# 1.net
KiCad netlist of a schematic drawn in Altium Designer
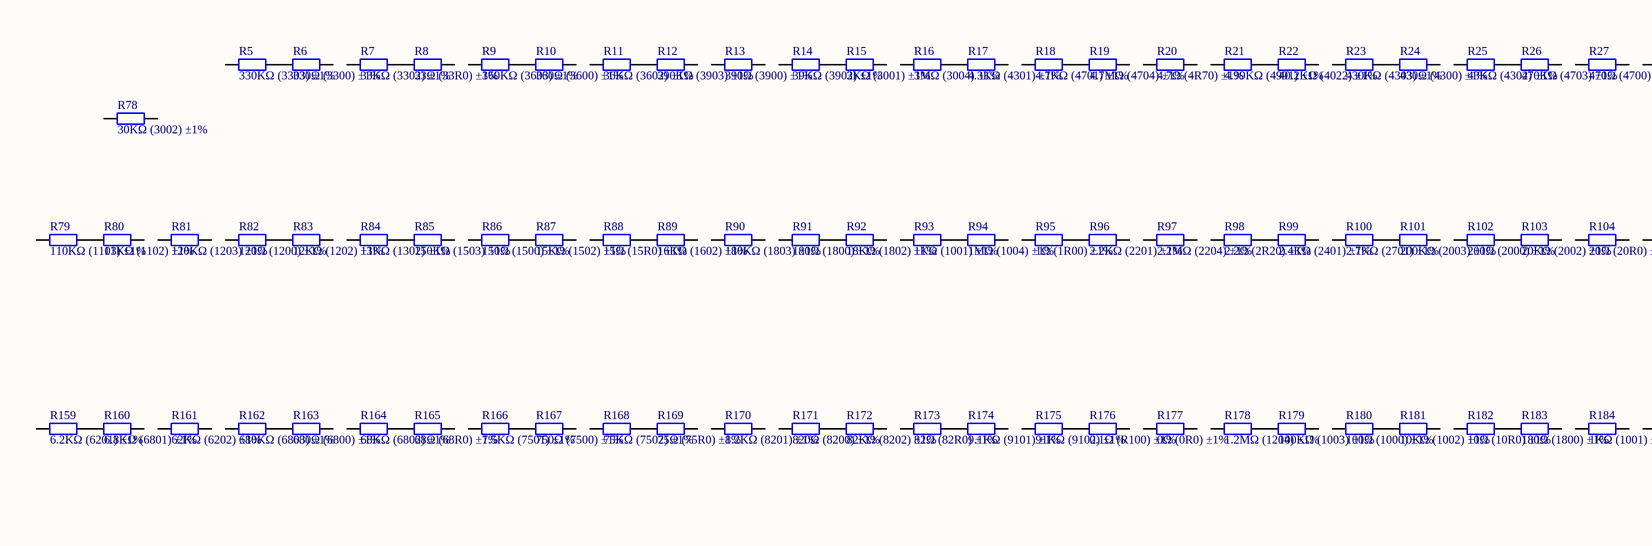
[diagram p0: 1.SchDoc, left]
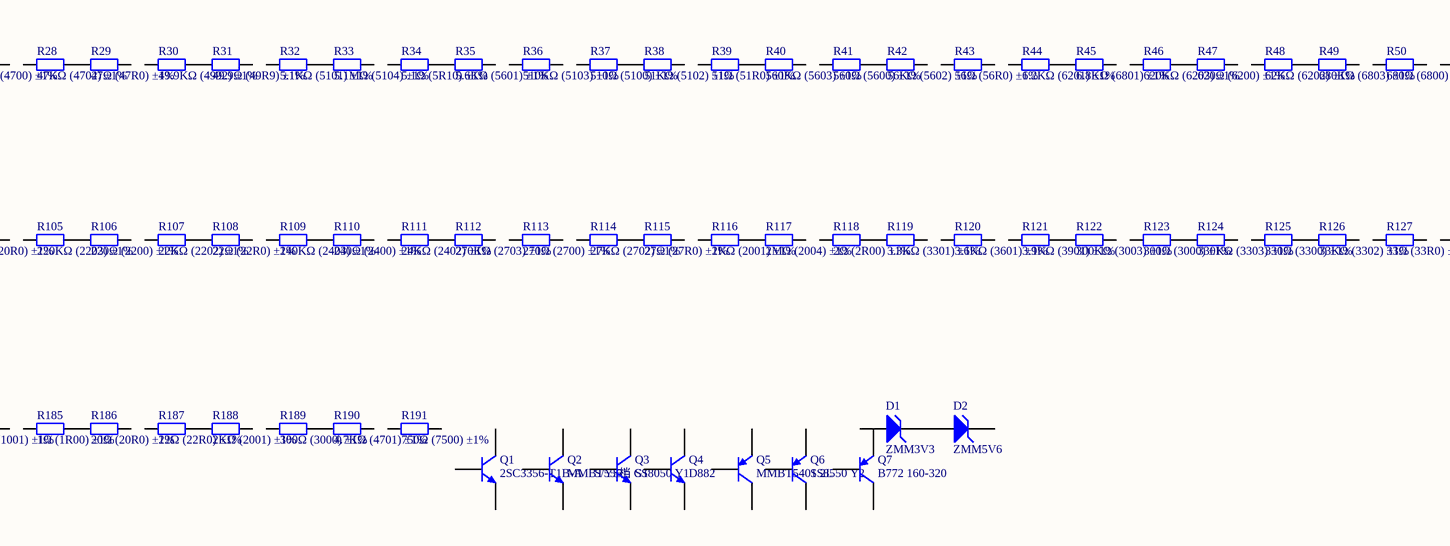
[diagram p1: 1.SchDoc, middle]
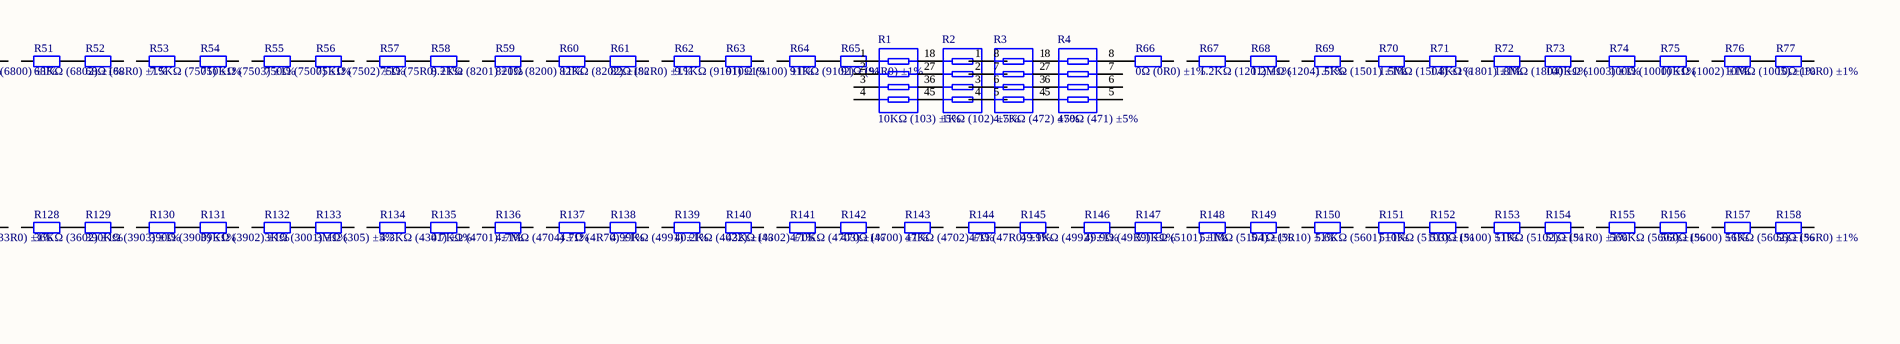
[diagram p2: 1.SchDoc, right]

(export (version "E")
  (design (tool "Eeschema 10.0.6"))
  (components
    (comp (ref "D1")
      (value "ZMM3V3")
      (footprint "LC-LL-34")
      (description "稳压二极管")
      (libsource (lib "Miscellaneous Devices LC") (part "LL-34 ZMM3V3"))
    )
    (comp (ref "D2")
      (value "ZMM5V6")
      (footprint "LC-LL-34")
      (description "稳压二极管")
      (libsource (lib "Miscellaneous Devices LC") (part "LL-34 ZMM5V6"))
    )
    (comp (ref "Q1")
      (value "2SC3356-T1B-A    S/YS档")
      (footprint "LC-SOT-23(SOT-23-3)")
      (description "三极管")
      (libsource (lib "Miscellaneous Devices LC") (part "SOT-23 2SC3356-T1B-A    S/YS档"))
    )
    (comp (ref "Q2")
      (value "MMBT5551  G1")
      (footprint "LC-SOT-23(SOT-23-3)")
      (description "三极管")
      (libsource (lib "Miscellaneous Devices LC") (part "SOT-23 MMBT5551  G1"))
    )
    (comp (ref "Q3")
      (value "SS8050 Y1")
      (footprint "LC-SOT-23(SOT-23-3)")
      (description "三极管")
      (libsource (lib "Miscellaneous Devices LC") (part "SOT-23 SS8050 Y1"))
    )
    (comp (ref "Q4")
      (value "D882")
      (footprint "LC-SOT-89(SOT-89-3)")
      (description "三极管")
      (libsource (lib "Miscellaneous Devices LC") (part "SOT-89 D882"))
    )
    (comp (ref "Q5")
      (value "MMBT5401 2L")
      (footprint "LC-SOT-23(SOT-23-3)")
      (description "三极管")
      (libsource (lib "Miscellaneous Devices LC") (part "SOT-23 MMBT5401 2L"))
    )
    (comp (ref "Q6")
      (value "SS8550 Y2")
      (footprint "LC-SOT-23(SOT-23-3)")
      (description "三极管")
      (libsource (lib "Miscellaneous Devices LC") (part "SOT-23 SS8550 Y2"))
    )
    (comp (ref "Q7")
      (value "B772 160-320")
      (footprint "LC-SOT-89(SOT-89-3)")
      (description "三极管")
      (libsource (lib "Miscellaneous Devices LC") (part "SOT-89 B772 160-320"))
    )
    (comp (ref "R1")
      (value "10KΩ (103) ±5%")
      (footprint "LC-0603_Rx4")
      (description "贴片排阻")
      (libsource (lib "Miscellaneous Devices LC") (part "0603*4  10KΩ (103) 5%"))
    )
    (comp (ref "R2")
      (value "1KΩ (102) ±5%")
      (footprint "LC-0603_Rx4")
      (description "贴片排阻")
      (libsource (lib "Miscellaneous Devices LC") (part "0603*4  1KΩ (102) 5%"))
    )
    (comp (ref "R3")
      (value "4.7KΩ (472) ±5%")
      (footprint "LC-0603_Rx4")
      (description "贴片排阻")
      (libsource (lib "Miscellaneous Devices LC") (part "0603*4  4.7KΩ (472) 5%"))
    )
    (comp (ref "R4")
      (value "470Ω (471) ±5%")
      (footprint "LC-0603_Rx4")
      (description "贴片排阻")
      (libsource (lib "Miscellaneous Devices LC") (part "0603*4 470Ω (471) 5%"))
    )
    (comp (ref "R5")
      (value "330KΩ (3303) ±1%")
      (footprint "LC-0603_R")
      (description "贴片电阻")
      (libsource (lib "Miscellaneous Devices LC") (part "0603 330KΩ (3303) 1%"))
    )
    (comp (ref "R6")
      (value "330Ω (3300) ±1%")
      (footprint "LC-0603_R")
      (description "贴片电阻")
      (libsource (lib "Miscellaneous Devices LC") (part "0603 330Ω (3300) 1%"))
    )
    (comp (ref "R7")
      (value "33KΩ (3302) ±1%")
      (footprint "LC-0603_R")
      (description "贴片电阻")
      (libsource (lib "Miscellaneous Devices LC") (part "0603 33KΩ (3302) 1%"))
    )
    (comp (ref "R8")
      (value "33Ω (33R0) ±1%")
      (footprint "LC-0603_R")
      (description "贴片电阻")
      (libsource (lib "Miscellaneous Devices LC") (part "0603 33Ω (33R0) 1%"))
    )
    (comp (ref "R9")
      (value "360KΩ (3603) ±1%")
      (footprint "LC-0603_R")
      (description "贴片电阻")
      (libsource (lib "Miscellaneous Devices LC") (part "0603 360KΩ (3603) 1%"))
    )
    (comp (ref "R10")
      (value "360Ω (3600) ±1%")
      (footprint "LC-0603_R")
      (description "贴片电阻")
      (libsource (lib "Miscellaneous Devices LC") (part "0603 360Ω (3600) 1%"))
    )
    (comp (ref "R11")
      (value "36KΩ (3602) ±1%")
      (footprint "LC-0603_R")
      (description "贴片电阻")
      (libsource (lib "Miscellaneous Devices LC") (part "0603 36KΩ (3602) 1%"))
    )
    (comp (ref "R12")
      (value "390KΩ (3903) ±1%")
      (footprint "LC-0603_R")
      (description "贴片电阻")
      (libsource (lib "Miscellaneous Devices LC") (part "0603 390KΩ (3903) 1%"))
    )
    (comp (ref "R13")
      (value "390Ω (3900) ±1%")
      (footprint "LC-0603_R")
      (description "贴片电阻")
      (libsource (lib "Miscellaneous Devices LC") (part "0603 390Ω (3900) 1%"))
    )
    (comp (ref "R14")
      (value "39KΩ (3902) ±1%")
      (footprint "LC-0603_R")
      (description "贴片电阻")
      (libsource (lib "Miscellaneous Devices LC") (part "0603 39KΩ (3902) 1%"))
    )
    (comp (ref "R15")
      (value "3KΩ (3001) ±1%")
      (footprint "LC-0603_R")
      (description "贴片电阻")
      (libsource (lib "Miscellaneous Devices LC") (part "0603 3KΩ (3001) 1%"))
    )
    (comp (ref "R16")
      (value "3MΩ (3004) ±1%")
      (footprint "LC-0603_R")
      (description "贴片电阻")
      (libsource (lib "Miscellaneous Devices LC") (part "0603 3MΩ (3004) 1%"))
    )
    (comp (ref "R17")
      (value "4.3KΩ (4301) ±1%")
      (footprint "LC-0603_R")
      (description "贴片电阻")
      (libsource (lib "Miscellaneous Devices LC") (part "0603 4.3KΩ (4301) 1%"))
    )
    (comp (ref "R18")
      (value "4.7KΩ (4701) ±1%")
      (footprint "LC-0603_R")
      (description "贴片电阻")
      (libsource (lib "Miscellaneous Devices LC") (part "0603 4.7KΩ (4701) 1%"))
    )
    (comp (ref "R19")
      (value "4.7MΩ (4704) ±1%")
      (footprint "LC-0603_R")
      (description "贴片电阻")
      (libsource (lib "Miscellaneous Devices LC") (part "0603 4.7MΩ (4704) 1%"))
    )
    (comp (ref "R20")
      (value "4.7Ω (4R70) ±1%")
      (footprint "LC-0603_R")
      (description "贴片电阻")
      (libsource (lib "Miscellaneous Devices LC") (part "0603 4.7Ω (4R70) 1%"))
    )
    (comp (ref "R21")
      (value "4.99KΩ (4991) ±1%")
      (footprint "LC-0603_R")
      (description "贴片电阻")
      (libsource (lib "Miscellaneous Devices LC") (part "0603 4.99KΩ (4991) 1%"))
    )
    (comp (ref "R22")
      (value "40.2KΩ (4022) ±1%")
      (footprint "LC-0603_R")
      (description "贴片电阻")
      (libsource (lib "Miscellaneous Devices LC") (part "0603 40.2KΩ (4022) 1%"))
    )
    (comp (ref "R23")
      (value "430KΩ (4303) ±1%")
      (footprint "LC-0603_R")
      (description "贴片电阻")
      (libsource (lib "Miscellaneous Devices LC") (part "0603 430KΩ (4303) 1%"))
    )
    (comp (ref "R24")
      (value "430Ω (4300) ±1%")
      (footprint "LC-0603_R")
      (description "贴片电阻")
      (libsource (lib "Miscellaneous Devices LC") (part "0603 430Ω (4300) 1%"))
    )
    (comp (ref "R25")
      (value "43KΩ (4302) ±1%")
      (footprint "LC-0603_R")
      (description "贴片电阻")
      (libsource (lib "Miscellaneous Devices LC") (part "0603 43KΩ (4302) 1%"))
    )
    (comp (ref "R26")
      (value "470KΩ (4703) ±1%")
      (footprint "LC-0603_R")
      (description "贴片电阻")
      (libsource (lib "Miscellaneous Devices LC") (part "0603 470KΩ (4703) 1%"))
    )
    (comp (ref "R27")
      (value "470Ω (4700) ±1%")
      (footprint "LC-0603_R")
      (description "贴片电阻")
      (libsource (lib "Miscellaneous Devices LC") (part "0603 470Ω (4700) 1%"))
    )
    (comp (ref "R28")
      (value "47KΩ (4702) ±1%")
      (footprint "LC-0603_R")
      (description "贴片电阻")
      (libsource (lib "Miscellaneous Devices LC") (part "0603 47KΩ (4702) 1%"))
    )
    (comp (ref "R29")
      (value "47Ω (47R0) ±1%")
      (footprint "LC-0603_R")
      (description "贴片电阻")
      (libsource (lib "Miscellaneous Devices LC") (part "0603 47Ω (47R0) 1%"))
    )
    (comp (ref "R30")
      (value "49.9KΩ (4992) ±1%")
      (footprint "LC-0603_R")
      (description "贴片电阻")
      (libsource (lib "Miscellaneous Devices LC") (part "0603 49.9KΩ (4992) 1%"))
    )
    (comp (ref "R31")
      (value "49.9Ω (49R9) ±1%")
      (footprint "LC-0603_R")
      (description "贴片电阻")
      (libsource (lib "Miscellaneous Devices LC") (part "0603 49.9Ω (49R9) 1%"))
    )
    (comp (ref "R32")
      (value "5.1KΩ (5101) ±1%")
      (footprint "LC-0603_R")
      (description "贴片电阻")
      (libsource (lib "Miscellaneous Devices LC") (part "0603 5.1KΩ (5101) 1%"))
    )
    (comp (ref "R33")
      (value "5.1MΩ (5104) ±1%")
      (footprint "LC-0603_R")
      (description "贴片电阻")
      (libsource (lib "Miscellaneous Devices LC") (part "0603 5.1MΩ (5104) 1%"))
    )
    (comp (ref "R34")
      (value "5.1Ω (5R10) ±1%")
      (footprint "LC-0603_R")
      (description "贴片电阻")
      (libsource (lib "Miscellaneous Devices LC") (part "0603 5.1Ω (5R10) 1%"))
    )
    (comp (ref "R35")
      (value "5.6KΩ (5601) ±1%")
      (footprint "LC-0603_R")
      (description "贴片电阻")
      (libsource (lib "Miscellaneous Devices LC") (part "0603 5.6KΩ (5601) 1%"))
    )
    (comp (ref "R36")
      (value "510KΩ (5103) ±1%")
      (footprint "LC-0603_R")
      (description "贴片电阻")
      (libsource (lib "Miscellaneous Devices LC") (part "0603 510KΩ (5103) 1%"))
    )
    (comp (ref "R37")
      (value "510Ω (5100) ±1%")
      (footprint "LC-0603_R")
      (description "贴片电阻")
      (libsource (lib "Miscellaneous Devices LC") (part "0603 510Ω (5100) 1%"))
    )
    (comp (ref "R38")
      (value "51KΩ (5102) ±1%")
      (footprint "LC-0603_R")
      (description "贴片电阻")
      (libsource (lib "Miscellaneous Devices LC") (part "0603 51KΩ (5102) 1%"))
    )
    (comp (ref "R39")
      (value "51Ω (51R0) ±1%")
      (footprint "LC-0603_R")
      (description "贴片电阻")
      (libsource (lib "Miscellaneous Devices LC") (part "0603 51Ω (51R0) 1%"))
    )
    (comp (ref "R40")
      (value "560KΩ (5603) ±1%")
      (footprint "LC-0603_R")
      (description "贴片电阻")
      (libsource (lib "Miscellaneous Devices LC") (part "0603 560KΩ (5603) 1%"))
    )
    (comp (ref "R41")
      (value "560Ω (5600) ±1%")
      (footprint "LC-0603_R")
      (description "贴片电阻")
      (libsource (lib "Miscellaneous Devices LC") (part "0603 560Ω (5600) 1%"))
    )
    (comp (ref "R42")
      (value "56KΩ (5602) ±1%")
      (footprint "LC-0603_R")
      (description "贴片电阻")
      (libsource (lib "Miscellaneous Devices LC") (part "0603 56KΩ (5602) 1%"))
    )
    (comp (ref "R43")
      (value "56Ω (56R0) ±1%")
      (footprint "LC-0603_R")
      (description "贴片电阻")
      (libsource (lib "Miscellaneous Devices LC") (part "0603 56Ω (56R0) 1%"))
    )
    (comp (ref "R44")
      (value "6.2KΩ (6201) ±1%")
      (footprint "LC-0603_R")
      (description "贴片电阻")
      (libsource (lib "Miscellaneous Devices LC") (part "0603 6.2KΩ (6201) 1%"))
    )
    (comp (ref "R45")
      (value "6.8KΩ (6801) ±1%")
      (footprint "LC-0603_R")
      (description "贴片电阻")
      (libsource (lib "Miscellaneous Devices LC") (part "0603 6.8KΩ (6801) 1%"))
    )
    (comp (ref "R46")
      (value "620KΩ (6203) ±1%")
      (footprint "LC-0603_R")
      (description "贴片电阻")
      (libsource (lib "Miscellaneous Devices LC") (part "0603 620KΩ (6203) 1%"))
    )
    (comp (ref "R47")
      (value "620Ω (6200) ±1%")
      (footprint "LC-0603_R")
      (description "贴片电阻")
      (libsource (lib "Miscellaneous Devices LC") (part "0603 620Ω (6200) 1%"))
    )
    (comp (ref "R48")
      (value "62KΩ (6202) ±1%")
      (footprint "LC-0603_R")
      (description "贴片电阻")
      (libsource (lib "Miscellaneous Devices LC") (part "0603 62KΩ (6202) 1%"))
    )
    (comp (ref "R49")
      (value "680KΩ (6803) ±1%")
      (footprint "LC-0603_R")
      (description "贴片电阻")
      (libsource (lib "Miscellaneous Devices LC") (part "0603 680KΩ (6803) 1%"))
    )
    (comp (ref "R50")
      (value "680Ω (6800) ±1%")
      (footprint "LC-0603_R")
      (description "贴片电阻")
      (libsource (lib "Miscellaneous Devices LC") (part "0603 680Ω (6800) 1%"))
    )
    (comp (ref "R51")
      (value "68KΩ (6802) ±1%")
      (footprint "LC-0603_R")
      (description "贴片电阻")
      (libsource (lib "Miscellaneous Devices LC") (part "0603 68KΩ (6802) 1%"))
    )
    (comp (ref "R52")
      (value "68Ω (68R0) ±1%")
      (footprint "LC-0603_R")
      (description "贴片电阻")
      (libsource (lib "Miscellaneous Devices LC") (part "0603 68Ω (68R0) 1%"))
    )
    (comp (ref "R53")
      (value "7.5KΩ (7501) ±1%")
      (footprint "LC-0603_R")
      (description "贴片电阻")
      (libsource (lib "Miscellaneous Devices LC") (part "0603 7.5KΩ (7501) 1%"))
    )
    (comp (ref "R54")
      (value "750KΩ (7503) ±1%")
      (footprint "LC-0603_R")
      (description "贴片电阻")
      (libsource (lib "Miscellaneous Devices LC") (part "0603 750KΩ (7503) 1%"))
    )
    (comp (ref "R55")
      (value "750Ω (7500) ±1%")
      (footprint "LC-0603_R")
      (description "贴片电阻")
      (libsource (lib "Miscellaneous Devices LC") (part "0603 750Ω (7500) 1%"))
    )
    (comp (ref "R56")
      (value "75KΩ (7502) ±1%")
      (footprint "LC-0603_R")
      (description "贴片电阻")
      (libsource (lib "Miscellaneous Devices LC") (part "0603 75KΩ (7502) 1%"))
    )
    (comp (ref "R57")
      (value "75Ω (75R0) ±1%")
      (footprint "LC-0603_R")
      (description "贴片电阻")
      (libsource (lib "Miscellaneous Devices LC") (part "0603 75Ω (75R0) 1%"))
    )
    (comp (ref "R58")
      (value "8.2KΩ (8201) ±1%")
      (footprint "LC-0603_R")
      (description "贴片电阻")
      (libsource (lib "Miscellaneous Devices LC") (part "0603 8.2KΩ (8201) 1%"))
    )
    (comp (ref "R59")
      (value "820Ω (8200) ±1%")
      (footprint "LC-0603_R")
      (description "贴片电阻")
      (libsource (lib "Miscellaneous Devices LC") (part "0603 820Ω (8200) 1%"))
    )
    (comp (ref "R60")
      (value "82KΩ (8202) ±1%")
      (footprint "LC-0603_R")
      (description "贴片电阻")
      (libsource (lib "Miscellaneous Devices LC") (part "0603 82KΩ (8202) 1%"))
    )
    (comp (ref "R61")
      (value "82Ω (82R0) ±1%")
      (footprint "LC-0603_R")
      (description "贴片电阻")
      (libsource (lib "Miscellaneous Devices LC") (part "0603 82Ω (82R0) 1%"))
    )
    (comp (ref "R62")
      (value "9.1KΩ (9101) ±1%")
      (footprint "LC-0603_R")
      (description "贴片电阻")
      (libsource (lib "Miscellaneous Devices LC") (part "0603 9.1KΩ (9101) 1%"))
    )
    (comp (ref "R63")
      (value "910Ω (9100) ±1%")
      (footprint "LC-0603_R")
      (description "贴片电阻")
      (libsource (lib "Miscellaneous Devices LC") (part "0603 910Ω (9100) 1%"))
    )
    (comp (ref "R64")
      (value "91KΩ (9102) ±1%")
      (footprint "LC-0603_R")
      (description "贴片电阻")
      (libsource (lib "Miscellaneous Devices LC") (part "0603 91KΩ (9102) 1%"))
    )
    (comp (ref "R65")
      (value "91Ω (91R0) ±1%")
      (footprint "LC-0603_R")
      (description "贴片电阻")
      (libsource (lib "Miscellaneous Devices LC") (part "0603 91Ω (91R0) 1%"))
    )
    (comp (ref "R66")
      (value "0Ω (0R0) ±1%")
      (footprint "LC-0805_R")
      (description "贴片电阻")
      (libsource (lib "Miscellaneous Devices LC") (part "0805 0Ω (0R0) 1%"))
    )
    (comp (ref "R67")
      (value "1.2KΩ (1201) ±1%")
      (footprint "LC-0805_R")
      (description "贴片电阻")
      (libsource (lib "Miscellaneous Devices LC") (part "0805 1.2KΩ (1201) 1%"))
    )
    (comp (ref "R68")
      (value "1.2MΩ (1204) ±1%")
      (footprint "LC-0805_R")
      (description "贴片电阻")
      (libsource (lib "Miscellaneous Devices LC") (part "0805 1.2MΩ (1204) 1%"))
    )
    (comp (ref "R69")
      (value "1.5KΩ (1501) ±1%")
      (footprint "LC-0805_R")
      (description "贴片电阻")
      (libsource (lib "Miscellaneous Devices LC") (part "0805 1.5KΩ (1501) 1%"))
    )
    (comp (ref "R70")
      (value "1.5MΩ (1504) ±1%")
      (footprint "LC-0805_R")
      (description "贴片电阻")
      (libsource (lib "Miscellaneous Devices LC") (part "0805 1.5MΩ (1504) 1%"))
    )
    (comp (ref "R71")
      (value "1.8KΩ (1801) ±1%")
      (footprint "LC-0805_R")
      (description "贴片电阻")
      (libsource (lib "Miscellaneous Devices LC") (part "0805 1.8KΩ (1801) 1%"))
    )
    (comp (ref "R72")
      (value "1.8MΩ (1804) ±1%")
      (footprint "LC-0805_R")
      (description "贴片电阻")
      (libsource (lib "Miscellaneous Devices LC") (part "0805 1.8MΩ (1804) 1%"))
    )
    (comp (ref "R73")
      (value "100KΩ (1003) ±1%")
      (footprint "LC-0805_R")
      (description "贴片电阻")
      (libsource (lib "Miscellaneous Devices LC") (part "0805 100KΩ (1003) 1%"))
    )
    (comp (ref "R74")
      (value "100Ω (1000) ±1%")
      (footprint "LC-0805_R")
      (description "贴片电阻")
      (libsource (lib "Miscellaneous Devices LC") (part "0805 100Ω (1000) 1%"))
    )
    (comp (ref "R75")
      (value "10KΩ (1002) ±1%")
      (footprint "LC-0805_R")
      (description "贴片电阻")
      (libsource (lib "Miscellaneous Devices LC") (part "0805 10KΩ (1002) 1%"))
    )
    (comp (ref "R76")
      (value "10MΩ (1005) ±1%")
      (footprint "LC-0805_R")
      (description "贴片电阻")
      (libsource (lib "Miscellaneous Devices LC") (part "0805 10MΩ (1005) 1%"))
    )
    (comp (ref "R77")
      (value "10Ω (10R0) ±1%")
      (footprint "LC-0805_R")
      (description "贴片电阻")
      (libsource (lib "Miscellaneous Devices LC") (part "0805 10Ω (10R0) 1%"))
    )
    (comp (ref "R78")
      (value "30KΩ (3002) ±1%")
      (footprint "LC-0603_R")
      (description "贴片电阻")
      (libsource (lib "Miscellaneous Devices LC") (part "0603 30KΩ (3002) 1%"))
    )
    (comp (ref "R79")
      (value "110KΩ (1103) ±1%")
      (footprint "LC-0805_R")
      (description "贴片电阻")
      (libsource (lib "Miscellaneous Devices LC") (part "0805 110KΩ (1103) 1%"))
    )
    (comp (ref "R80")
      (value "11KΩ (1102) ±1%")
      (footprint "LC-0805_R")
      (description "贴片电阻")
      (libsource (lib "Miscellaneous Devices LC") (part "0805 11KΩ (1102) 1%"))
    )
    (comp (ref "R81")
      (value "120KΩ (1203) ±1%")
      (footprint "LC-0805_R")
      (description "贴片电阻")
      (libsource (lib "Miscellaneous Devices LC") (part "0805 120KΩ (1203) 1%"))
    )
    (comp (ref "R82")
      (value "120Ω (1200) ±1%")
      (footprint "LC-0805_R")
      (description "贴片电阻")
      (libsource (lib "Miscellaneous Devices LC") (part "0805 120Ω (1200) 1%"))
    )
    (comp (ref "R83")
      (value "12KΩ (1202) ±1%")
      (footprint "LC-0805_R")
      (description "贴片电阻")
      (libsource (lib "Miscellaneous Devices LC") (part "0805 12KΩ (1202) 1%"))
    )
    (comp (ref "R84")
      (value "13KΩ (1302) ±1%")
      (footprint "LC-0805_R")
      (description "贴片电阻")
      (libsource (lib "Miscellaneous Devices LC") (part "0805 13KΩ (1302) 1%"))
    )
    (comp (ref "R85")
      (value "150KΩ (1503) ±1%")
      (footprint "LC-0805_R")
      (description "贴片电阻")
      (libsource (lib "Miscellaneous Devices LC") (part "0805 150KΩ (1503) 1%"))
    )
    (comp (ref "R86")
      (value "150Ω (1500) ±1%")
      (footprint "LC-0805_R")
      (description "贴片电阻")
      (libsource (lib "Miscellaneous Devices LC") (part "0805 150Ω (1500) 1%"))
    )
    (comp (ref "R87")
      (value "15KΩ (1502) ±1%")
      (footprint "LC-0805_R")
      (description "贴片电阻")
      (libsource (lib "Miscellaneous Devices LC") (part "0805 15KΩ (1502) 1%"))
    )
    (comp (ref "R88")
      (value "15Ω (15R0) ±1%")
      (footprint "LC-0805_R")
      (description "贴片电阻")
      (libsource (lib "Miscellaneous Devices LC") (part "0805 15Ω (15R0) 1%"))
    )
    (comp (ref "R89")
      (value "16KΩ (1602) ±1%")
      (footprint "LC-0805_R")
      (description "贴片电阻")
      (libsource (lib "Miscellaneous Devices LC") (part "0805 16KΩ (1602) 1%"))
    )
    (comp (ref "R90")
      (value "180KΩ (1803) ±1%")
      (footprint "LC-0805_R")
      (description "贴片电阻")
      (libsource (lib "Miscellaneous Devices LC") (part "0805 180KΩ (1803) 1%"))
    )
    (comp (ref "R91")
      (value "180Ω (1800) ±1%")
      (footprint "LC-0805_R")
      (description "贴片电阻")
      (libsource (lib "Miscellaneous Devices LC") (part "0805 180Ω (1800) 1%"))
    )
    (comp (ref "R92")
      (value "18KΩ (1802) ±1%")
      (footprint "LC-0805_R")
      (description "贴片电阻")
      (libsource (lib "Miscellaneous Devices LC") (part "0805 18KΩ (1802) 1%"))
    )
    (comp (ref "R93")
      (value "1KΩ (1001) ±1%")
      (footprint "LC-0805_R")
      (description "贴片电阻")
      (libsource (lib "Miscellaneous Devices LC") (part "0805 1KΩ (1001) 1%"))
    )
    (comp (ref "R94")
      (value "1MΩ (1004) ±1%")
      (footprint "LC-0805_R")
      (description "贴片电阻")
      (libsource (lib "Miscellaneous Devices LC") (part "0805 1MΩ (1004) 1%"))
    )
    (comp (ref "R95")
      (value "1Ω (1R00) ±1%")
      (footprint "LC-0805_R")
      (description "贴片电阻")
      (libsource (lib "Miscellaneous Devices LC") (part "0805 1Ω (1R00) 1%"))
    )
    (comp (ref "R96")
      (value "2.2KΩ (2201) ±1%")
      (footprint "LC-0805_R")
      (description "贴片电阻")
      (libsource (lib "Miscellaneous Devices LC") (part "0805 2.2KΩ (2201) 1%"))
    )
    (comp (ref "R97")
      (value "2.2MΩ (2204) ±1%")
      (footprint "LC-0805_R")
      (description "贴片电阻")
      (libsource (lib "Miscellaneous Devices LC") (part "0805 2.2MΩ (2204) 1%"))
    )
    (comp (ref "R98")
      (value "2.2Ω (2R20) ±1%")
      (footprint "LC-0805_R")
      (description "贴片电阻")
      (libsource (lib "Miscellaneous Devices LC") (part "0805 2.2Ω (2R20) 1%"))
    )
    (comp (ref "R99")
      (value "2.4KΩ (2401) ±1%")
      (footprint "LC-0805_R")
      (description "贴片电阻")
      (libsource (lib "Miscellaneous Devices LC") (part "0805 2.4KΩ (2401) 1%"))
    )
    (comp (ref "R100")
      (value "2.7KΩ (2701) ±1%")
      (footprint "LC-0805_R")
      (description "贴片电阻")
      (libsource (lib "Miscellaneous Devices LC") (part "0805 2.7KΩ (2701) 1%"))
    )
    (comp (ref "R101")
      (value "200KΩ (2003) ±1%")
      (footprint "LC-0805_R")
      (description "贴片电阻")
      (libsource (lib "Miscellaneous Devices LC") (part "0805 200KΩ (2003) 1%"))
    )
    (comp (ref "R102")
      (value "200Ω (2000) ±1%")
      (footprint "LC-0805_R")
      (description "贴片电阻")
      (libsource (lib "Miscellaneous Devices LC") (part "0805 200Ω (2000) 1%"))
    )
    (comp (ref "R103")
      (value "20KΩ (2002) ±1%")
      (footprint "LC-0805_R")
      (description "贴片电阻")
      (libsource (lib "Miscellaneous Devices LC") (part "0805 20KΩ (2002) 1%"))
    )
    (comp (ref "R104")
      (value "20Ω (20R0) ±1%")
      (footprint "LC-0805_R")
      (description "贴片电阻")
      (libsource (lib "Miscellaneous Devices LC") (part "0805 20Ω (20R0) 1%"))
    )
    (comp (ref "R105")
      (value "220KΩ (2203) ±1%")
      (footprint "LC-0805_R")
      (description "贴片电阻")
      (libsource (lib "Miscellaneous Devices LC") (part "0805 220KΩ (2203) 1%"))
    )
    (comp (ref "R106")
      (value "220Ω (2200) ±1%")
      (footprint "LC-0805_R")
      (description "贴片电阻")
      (libsource (lib "Miscellaneous Devices LC") (part "0805 220Ω (2200) 1%"))
    )
    (comp (ref "R107")
      (value "22KΩ (2202) ±1%")
      (footprint "LC-0805_R")
      (description "贴片电阻")
      (libsource (lib "Miscellaneous Devices LC") (part "0805 22KΩ (2202) 1%"))
    )
    (comp (ref "R108")
      (value "22Ω (22R0) ±1%")
      (footprint "LC-0805_R")
      (description "贴片电阻")
      (libsource (lib "Miscellaneous Devices LC") (part "0805 22Ω (22R0) 1%"))
    )
    (comp (ref "R109")
      (value "240KΩ (2403) ±1%")
      (footprint "LC-0805_R")
      (description "贴片电阻")
      (libsource (lib "Miscellaneous Devices LC") (part "0805 240KΩ (2403) 1%"))
    )
    (comp (ref "R110")
      (value "240Ω (2400) ±1%")
      (footprint "LC-0805_R")
      (description "贴片电阻")
      (libsource (lib "Miscellaneous Devices LC") (part "0805 240Ω (2400) 1%"))
    )
    (comp (ref "R111")
      (value "24KΩ (2402) ±1%")
      (footprint "LC-0805_R")
      (description "贴片电阻")
      (libsource (lib "Miscellaneous Devices LC") (part "0805 24KΩ (2402) 1%"))
    )
    (comp (ref "R112")
      (value "270KΩ (2703) ±1%")
      (footprint "LC-0805_R")
      (description "贴片电阻")
      (libsource (lib "Miscellaneous Devices LC") (part "0805 270KΩ (2703) 1%"))
    )
    (comp (ref "R113")
      (value "270Ω (2700) ±1%")
      (footprint "LC-0805_R")
      (description "贴片电阻")
      (libsource (lib "Miscellaneous Devices LC") (part "0805 270Ω (2700) 1%"))
    )
    (comp (ref "R114")
      (value "27KΩ (2702) ±1%")
      (footprint "LC-0805_R")
      (description "贴片电阻")
      (libsource (lib "Miscellaneous Devices LC") (part "0805 27KΩ (2702) 1%"))
    )
    (comp (ref "R115")
      (value "27Ω (27R0) ±1%")
      (footprint "LC-0805_R")
      (description "贴片电阻")
      (libsource (lib "Miscellaneous Devices LC") (part "0805 27Ω (27R0) 1%"))
    )
    (comp (ref "R116")
      (value "2KΩ (2001) ±1%")
      (footprint "LC-0805_R")
      (description "贴片电阻")
      (libsource (lib "Miscellaneous Devices LC") (part "0805 2KΩ (2001) 1%"))
    )
    (comp (ref "R117")
      (value "2MΩ (2004) ±1%")
      (footprint "LC-0805_R")
      (description "贴片电阻")
      (libsource (lib "Miscellaneous Devices LC") (part "0805 2MΩ (2004) 1%"))
    )
    (comp (ref "R118")
      (value "2Ω (2R00) ±1%")
      (footprint "LC-0805_R")
      (description "贴片电阻")
      (libsource (lib "Miscellaneous Devices LC") (part "0805 2Ω (2R00) 1%"))
    )
    (comp (ref "R119")
      (value "3.3KΩ (3301) ±1%")
      (footprint "LC-0805_R")
      (description "贴片电阻")
      (libsource (lib "Miscellaneous Devices LC") (part "0805 3.3KΩ (3301) 1%"))
    )
    (comp (ref "R120")
      (value "3.6KΩ (3601) ±1%")
      (footprint "LC-0805_R")
      (description "贴片电阻")
      (libsource (lib "Miscellaneous Devices LC") (part "0805 3.6KΩ (3601) 1%"))
    )
    (comp (ref "R121")
      (value "3.9KΩ (3901) ±1%")
      (footprint "LC-0805_R")
      (description "贴片电阻")
      (libsource (lib "Miscellaneous Devices LC") (part "0805 3.9KΩ (3901) 1%"))
    )
    (comp (ref "R122")
      (value "300KΩ (3003) ±1%")
      (footprint "LC-0805_R")
      (description "贴片电阻")
      (libsource (lib "Miscellaneous Devices LC") (part "0805 300KΩ (3003) 1%"))
    )
    (comp (ref "R123")
      (value "300Ω (3000) ±1%")
      (footprint "LC-0805_R")
      (description "贴片电阻")
      (libsource (lib "Miscellaneous Devices LC") (part "0805 300Ω (3000) 1%"))
    )
    (comp (ref "R124")
      (value "330KΩ (3303) ±1%")
      (footprint "LC-0805_R")
      (description "贴片电阻")
      (libsource (lib "Miscellaneous Devices LC") (part "0805 330KΩ (3303) 1%"))
    )
    (comp (ref "R125")
      (value "330Ω (3300) ±1%")
      (footprint "LC-0805_R")
      (description "贴片电阻")
      (libsource (lib "Miscellaneous Devices LC") (part "0805 330Ω (3300) 1%"))
    )
    (comp (ref "R126")
      (value "33KΩ (3302) ±1%")
      (footprint "LC-0805_R")
      (description "贴片电阻")
      (libsource (lib "Miscellaneous Devices LC") (part "0805 33KΩ (3302) 1%"))
    )
    (comp (ref "R127")
      (value "33Ω (33R0) ±1%")
      (footprint "LC-0805_R")
      (description "贴片电阻")
      (libsource (lib "Miscellaneous Devices LC") (part "0805 33Ω (33R0) 1%"))
    )
    (comp (ref "R128")
      (value "36KΩ (3602) ±1%")
      (footprint "LC-0805_R")
      (description "贴片电阻")
      (libsource (lib "Miscellaneous Devices LC") (part "0805 36KΩ (3602) 1%"))
    )
    (comp (ref "R129")
      (value "390KΩ (3903) ±1%")
      (footprint "LC-0805_R")
      (description "贴片电阻")
      (libsource (lib "Miscellaneous Devices LC") (part "0805 390KΩ (3903) 1%"))
    )
    (comp (ref "R130")
      (value "390Ω (3900) ±1%")
      (footprint "LC-0805_R")
      (description "贴片电阻")
      (libsource (lib "Miscellaneous Devices LC") (part "0805 390Ω (3900) 1%"))
    )
    (comp (ref "R131")
      (value "39KΩ (3902) ±1%")
      (footprint "LC-0805_R")
      (description "贴片电阻")
      (libsource (lib "Miscellaneous Devices LC") (part "0805 39KΩ (3902) 1%"))
    )
    (comp (ref "R132")
      (value "3KΩ (3001) ±1%")
      (footprint "LC-0805_R")
      (description "贴片电阻")
      (libsource (lib "Miscellaneous Devices LC") (part "0805 3KΩ (3001) 1%"))
    )
    (comp (ref "R133")
      (value "3MΩ (305) ±5%")
      (footprint "LC-0805_R")
      (description "贴片电阻")
      (libsource (lib "Miscellaneous Devices LC") (part "0805 3MΩ (305) 5%"))
    )
    (comp (ref "R134")
      (value "4.3KΩ (4301) ±1%")
      (footprint "LC-0805_R")
      (description "贴片电阻")
      (libsource (lib "Miscellaneous Devices LC") (part "0805 4.3KΩ (4301) 1%"))
    )
    (comp (ref "R135")
      (value "4.7KΩ (4701) ±1%")
      (footprint "LC-0805_R")
      (description "贴片电阻")
      (libsource (lib "Miscellaneous Devices LC") (part "0805 4.7KΩ (4701) 1%"))
    )
    (comp (ref "R136")
      (value "4.7MΩ (4704) ±1%")
      (footprint "LC-0805_R")
      (description "贴片电阻")
      (libsource (lib "Miscellaneous Devices LC") (part "0805 4.7MΩ (4704) 1%"))
    )
    (comp (ref "R137")
      (value "4.7Ω (4R70) ±1%")
      (footprint "LC-0805_R")
      (description "贴片电阻")
      (libsource (lib "Miscellaneous Devices LC") (part "0805 4.7Ω (4R70) 1%"))
    )
    (comp (ref "R138")
      (value "4.99KΩ (4991) ±1%")
      (footprint "LC-0805_R")
      (description "贴片电阻")
      (libsource (lib "Miscellaneous Devices LC") (part "0805 4.99KΩ (4991) 1%"))
    )
    (comp (ref "R139")
      (value "40.2KΩ (4022) ±1%")
      (footprint "LC-0805_R")
      (description "贴片电阻")
      (libsource (lib "Miscellaneous Devices LC") (part "0805 40.2KΩ (4022) 1%"))
    )
    (comp (ref "R140")
      (value "43KΩ (4302) ±1%")
      (footprint "LC-0805_R")
      (description "贴片电阻")
      (libsource (lib "Miscellaneous Devices LC") (part "0805 43KΩ (4302) 1%"))
    )
    (comp (ref "R141")
      (value "470KΩ (4703) ±1%")
      (footprint "LC-0805_R")
      (description "贴片电阻")
      (libsource (lib "Miscellaneous Devices LC") (part "0805 470KΩ (4703) 1%"))
    )
    (comp (ref "R142")
      (value "470Ω (4700) ±1%")
      (footprint "LC-0805_R")
      (description "贴片电阻")
      (libsource (lib "Miscellaneous Devices LC") (part "0805 470Ω (4700) 1%"))
    )
    (comp (ref "R143")
      (value "47KΩ (4702) ±1%")
      (footprint "LC-0805_R")
      (description "贴片电阻")
      (libsource (lib "Miscellaneous Devices LC") (part "0805 47KΩ (4702) 1%"))
    )
    (comp (ref "R144")
      (value "47Ω (47R0) ±1%")
      (footprint "LC-0805_R")
      (description "贴片电阻")
      (libsource (lib "Miscellaneous Devices LC") (part "0805 47Ω (47R0) 1%"))
    )
    (comp (ref "R145")
      (value "49.9KΩ (4992) ±1%")
      (footprint "LC-0805_R")
      (description "贴片电阻")
      (libsource (lib "Miscellaneous Devices LC") (part "0805 49.9KΩ (4992) 1%"))
    )
    (comp (ref "R146")
      (value "49.9Ω (49R9) ±1%")
      (footprint "LC-0805_R")
      (description "贴片电阻")
      (libsource (lib "Miscellaneous Devices LC") (part "0805 49.9Ω (49R9) 1%"))
    )
    (comp (ref "R147")
      (value "5.1KΩ (5101) ±1%")
      (footprint "LC-0805_R")
      (description "贴片电阻")
      (libsource (lib "Miscellaneous Devices LC") (part "0805 5.1KΩ (5101) 1%"))
    )
    (comp (ref "R148")
      (value "5.1MΩ (5104) ±1%")
      (footprint "LC-0805_R")
      (description "贴片电阻")
      (libsource (lib "Miscellaneous Devices LC") (part "0805 5.1MΩ (5104) 1%"))
    )
    (comp (ref "R149")
      (value "5.1Ω (5R10) ±1%")
      (footprint "LC-0805_R")
      (description "贴片电阻")
      (libsource (lib "Miscellaneous Devices LC") (part "0805 5.1Ω (5R10) 1%"))
    )
    (comp (ref "R150")
      (value "5.6KΩ (5601) ±1%")
      (footprint "LC-0805_R")
      (description "贴片电阻")
      (libsource (lib "Miscellaneous Devices LC") (part "0805 5.6KΩ (5601) 1%"))
    )
    (comp (ref "R151")
      (value "510KΩ (5103) ±1%")
      (footprint "LC-0805_R")
      (description "贴片电阻")
      (libsource (lib "Miscellaneous Devices LC") (part "0805 510KΩ (5103) 1%"))
    )
    (comp (ref "R152")
      (value "510Ω (5100) ±1%")
      (footprint "LC-0805_R")
      (description "贴片电阻")
      (libsource (lib "Miscellaneous Devices LC") (part "0805 510Ω (5100) 1%"))
    )
    (comp (ref "R153")
      (value "51KΩ (5102) ±1%")
      (footprint "LC-0805_R")
      (description "贴片电阻")
      (libsource (lib "Miscellaneous Devices LC") (part "0805 51KΩ (5102) 1%"))
    )
    (comp (ref "R154")
      (value "51Ω (51R0) ±1%")
      (footprint "LC-0805_R")
      (description "贴片电阻")
      (libsource (lib "Miscellaneous Devices LC") (part "0805 51Ω (51R0) 1%"))
    )
    (comp (ref "R155")
      (value "560KΩ (5603) ±1%")
      (footprint "LC-0805_R")
      (description "贴片电阻")
      (libsource (lib "Miscellaneous Devices LC") (part "0805 560KΩ (5603) 1%"))
    )
    (comp (ref "R156")
      (value "560Ω (5600) ±1%")
      (footprint "LC-0805_R")
      (description "贴片电阻")
      (libsource (lib "Miscellaneous Devices LC") (part "0805 560Ω (5600) 1%"))
    )
    (comp (ref "R157")
      (value "56KΩ (5602) ±1%")
      (footprint "LC-0805_R")
      (description "贴片电阻")
      (libsource (lib "Miscellaneous Devices LC") (part "0805 56KΩ (5602) 1%"))
    )
    (comp (ref "R158")
      (value "56Ω (56R0) ±1%")
      (footprint "LC-0805_R")
      (description "贴片电阻")
      (libsource (lib "Miscellaneous Devices LC") (part "0805 56Ω (56R0) 1%"))
    )
    (comp (ref "R159")
      (value "6.2KΩ (6201) ±1%")
      (footprint "LC-0805_R")
      (description "贴片电阻")
      (libsource (lib "Miscellaneous Devices LC") (part "0805 6.2KΩ (6201) 1%"))
    )
    (comp (ref "R160")
      (value "6.8KΩ (6801) ±1%")
      (footprint "LC-0805_R")
      (description "贴片电阻")
      (libsource (lib "Miscellaneous Devices LC") (part "0805 6.8KΩ (6801) 1%"))
    )
    (comp (ref "R161")
      (value "62KΩ (6202) ±1%")
      (footprint "LC-0805_R")
      (description "贴片电阻")
      (libsource (lib "Miscellaneous Devices LC") (part "0805 62KΩ (6202) 1%"))
    )
    (comp (ref "R162")
      (value "680KΩ (6803) ±1%")
      (footprint "LC-0805_R")
      (description "贴片电阻")
      (libsource (lib "Miscellaneous Devices LC") (part "0805 680KΩ (6803) 1%"))
    )
    (comp (ref "R163")
      (value "680Ω (6800) ±1%")
      (footprint "LC-0805_R")
      (description "贴片电阻")
      (libsource (lib "Miscellaneous Devices LC") (part "0805 680Ω (6800) 1%"))
    )
    (comp (ref "R164")
      (value "68KΩ (6802) ±1%")
      (footprint "LC-0805_R")
      (description "贴片电阻")
      (libsource (lib "Miscellaneous Devices LC") (part "0805 68KΩ (6802) 1%"))
    )
    (comp (ref "R165")
      (value "68Ω (68R0) ±1%")
      (footprint "LC-0805_R")
      (description "贴片电阻")
      (libsource (lib "Miscellaneous Devices LC") (part "0805 68Ω (68R0) 1%"))
    )
    (comp (ref "R166")
      (value "7.5KΩ (7501) ±1%")
      (footprint "LC-0805_R")
      (description "贴片电阻")
      (libsource (lib "Miscellaneous Devices LC") (part "0805 7.5KΩ (7501) 1%"))
    )
    (comp (ref "R167")
      (value "750Ω (7500) ±1%")
      (footprint "LC-0805_R")
      (description "贴片电阻")
      (libsource (lib "Miscellaneous Devices LC") (part "0805 750Ω (7500) 1%"))
    )
    (comp (ref "R168")
      (value "75KΩ (7502) ±1%")
      (footprint "LC-0805_R")
      (description "贴片电阻")
      (libsource (lib "Miscellaneous Devices LC") (part "0805 75KΩ (7502) 1%"))
    )
    (comp (ref "R169")
      (value "75Ω (75R0) ±1%")
      (footprint "LC-0805_R")
      (description "贴片电阻")
      (libsource (lib "Miscellaneous Devices LC") (part "0805 75Ω (75R0) 1%"))
    )
    (comp (ref "R170")
      (value "8.2KΩ (8201) ±1%")
      (footprint "LC-0805_R")
      (description "贴片电阻")
      (libsource (lib "Miscellaneous Devices LC") (part "0805 8.2KΩ (8201) 1%"))
    )
    (comp (ref "R171")
      (value "820Ω (8200) ±1%")
      (footprint "LC-0805_R")
      (description "贴片电阻")
      (libsource (lib "Miscellaneous Devices LC") (part "0805 820Ω (8200) 1%"))
    )
    (comp (ref "R172")
      (value "82KΩ (8202) ±1%")
      (footprint "LC-0805_R")
      (description "贴片电阻")
      (libsource (lib "Miscellaneous Devices LC") (part "0805 82KΩ (8202) 1%"))
    )
    (comp (ref "R173")
      (value "82Ω (82R0) ±1%")
      (footprint "LC-0805_R")
      (description "贴片电阻")
      (libsource (lib "Miscellaneous Devices LC") (part "0805 82Ω (82R0) 1%"))
    )
    (comp (ref "R174")
      (value "9.1KΩ (9101) ±1%")
      (footprint "LC-0805_R")
      (description "贴片电阻")
      (libsource (lib "Miscellaneous Devices LC") (part "0805 9.1KΩ (9101) 1%"))
    )
    (comp (ref "R175")
      (value "91KΩ (9102) ±1%")
      (footprint "LC-0805_R")
      (description "贴片电阻")
      (libsource (lib "Miscellaneous Devices LC") (part "0805 91KΩ (9102) 1%"))
    )
    (comp (ref "R176")
      (value "0.1Ω (R100) ±1%")
      (footprint "LC-1206_R")
      (description "贴片电阻")
      (libsource (lib "Miscellaneous Devices LC") (part "1206 0.1Ω (R100) 1%"))
    )
    (comp (ref "R177")
      (value "0Ω (0R0) ±1%")
      (footprint "LC-1206_R")
      (description "贴片电阻")
      (libsource (lib "Miscellaneous Devices LC") (part "1206 0Ω (0R0) 1%"))
    )
    (comp (ref "R178")
      (value "1.2MΩ (1204) ±1%")
      (footprint "LC-1206_R")
      (description "贴片电阻")
      (libsource (lib "Miscellaneous Devices LC") (part "1206 1.2MΩ (1204) 1%"))
    )
    (comp (ref "R179")
      (value "100KΩ (1003) ±1%")
      (footprint "LC-1206_R")
      (description "贴片电阻")
      (libsource (lib "Miscellaneous Devices LC") (part "1206 100KΩ (1003) 1%"))
    )
    (comp (ref "R180")
      (value "100Ω (1000) ±1%")
      (footprint "LC-1206_R")
      (description "贴片电阻")
      (libsource (lib "Miscellaneous Devices LC") (part "1206 100Ω (1000) 1%"))
    )
    (comp (ref "R181")
      (value "10KΩ (1002) ±1%")
      (footprint "LC-1206_R")
      (description "贴片电阻")
      (libsource (lib "Miscellaneous Devices LC") (part "1206 10KΩ (1002) 1%"))
    )
    (comp (ref "R182")
      (value "10Ω (10R0) ±1%")
      (footprint "LC-1206_R")
      (description "贴片电阻")
      (libsource (lib "Miscellaneous Devices LC") (part "1206 10Ω (10R0) 1%"))
    )
    (comp (ref "R183")
      (value "180Ω (1800) ±1%")
      (footprint "LC-1206_R")
      (description "贴片电阻")
      (libsource (lib "Miscellaneous Devices LC") (part "1206 180Ω (1800) 1%"))
    )
    (comp (ref "R184")
      (value "1KΩ (1001) ±1%")
      (footprint "LC-1206_R")
      (description "贴片电阻")
      (libsource (lib "Miscellaneous Devices LC") (part "1206 1KΩ (1001) 1%"))
    )
    (comp (ref "R185")
      (value "1Ω (1R00) ±1%")
      (footprint "LC-1206_R")
      (description "贴片电阻")
      (libsource (lib "Miscellaneous Devices LC") (part "1206 1Ω (1R00) 1%"))
    )
    (comp (ref "R186")
      (value "20Ω (20R0) ±1%")
      (footprint "LC-1206_R")
      (description "贴片电阻")
      (libsource (lib "Miscellaneous Devices LC") (part "1206 20Ω (20R0) 1%"))
    )
    (comp (ref "R187")
      (value "22Ω (22R0) ±1%")
      (footprint "LC-1206_R")
      (description "贴片电阻")
      (libsource (lib "Miscellaneous Devices LC") (part "1206 22Ω (22R0) 1%"))
    )
    (comp (ref "R188")
      (value "2KΩ (2001) ±1%")
      (footprint "LC-1206_R")
      (description "贴片电阻")
      (libsource (lib "Miscellaneous Devices LC") (part "1206 2KΩ (2001) 1%"))
    )
    (comp (ref "R189")
      (value "300Ω (3000) ±1%")
      (footprint "LC-1206_R")
      (description "贴片电阻")
      (libsource (lib "Miscellaneous Devices LC") (part "1206 300Ω (3000) 1%"))
    )
    (comp (ref "R190")
      (value "4.7KΩ (4701) ±1%")
      (footprint "LC-1206_R")
      (description "贴片电阻")
      (libsource (lib "Miscellaneous Devices LC") (part "1206 4.7KΩ (4701) 1%"))
    )
    (comp (ref "R191")
      (value "750Ω (7500) ±1%")
      (footprint "LC-1206_R")
      (description "贴片电阻")
      (libsource (lib "Miscellaneous Devices LC") (part "1206 750Ω (7500) 1%"))
    )
  )
  (nets
    (net (code "1") (name "Net-(D1-K)") (class "Default")
      (node (ref "D1") (pin "2") (pinfunction "K_2") (pintype "passive"))
      (node (ref "D2") (pin "1") (pinfunction "A_1") (pintype "passive"))
    )
    (net (code "2") (name "Net-(R4-Pad8)") (class "Default")
      (node (ref "R4") (pin "8") (pinfunction "8_8") (pintype "passive"))
      (node (ref "R66") (pin "1") (pinfunction "1_1") (pintype "passive"))
    )
    (net (code "3") (name "Net-(R5-Pad2)") (class "Default")
      (node (ref "R5") (pin "2") (pinfunction "2_2") (pintype "passive"))
      (node (ref "R6") (pin "1") (pinfunction "1_1") (pintype "passive"))
    )
    (net (code "4") (name "Net-(R7-Pad2)") (class "Default")
      (node (ref "R7") (pin "2") (pinfunction "2_2") (pintype "passive"))
      (node (ref "R8") (pin "1") (pinfunction "1_1") (pintype "passive"))
    )
    (net (code "5") (name "Net-(R10-Pad1)") (class "Default")
      (node (ref "R10") (pin "1") (pinfunction "1_1") (pintype "passive"))
      (node (ref "R9") (pin "2") (pinfunction "2_2") (pintype "passive"))
    )
    (net (code "6") (name "Net-(R11-Pad2)") (class "Default")
      (node (ref "R11") (pin "2") (pinfunction "2_2") (pintype "passive"))
      (node (ref "R12") (pin "1") (pinfunction "1_1") (pintype "passive"))
    )
    (net (code "7") (name "Net-(R14-Pad2)") (class "Default")
      (node (ref "R14") (pin "2") (pinfunction "2_2") (pintype "passive"))
      (node (ref "R15") (pin "1") (pinfunction "1_1") (pintype "passive"))
    )
    (net (code "8") (name "Net-(R16-Pad2)") (class "Default")
      (node (ref "R16") (pin "2") (pinfunction "2_2") (pintype "passive"))
      (node (ref "R17") (pin "1") (pinfunction "1_1") (pintype "passive"))
    )
    (net (code "9") (name "Net-(R18-Pad2)") (class "Default")
      (node (ref "R18") (pin "2") (pinfunction "2_2") (pintype "passive"))
      (node (ref "R19") (pin "1") (pinfunction "1_1") (pintype "passive"))
    )
    (net (code "10") (name "Net-(R21-Pad2)") (class "Default")
      (node (ref "R21") (pin "2") (pinfunction "2_2") (pintype "passive"))
      (node (ref "R22") (pin "1") (pinfunction "1_1") (pintype "passive"))
    )
    (net (code "11") (name "Net-(R23-Pad2)") (class "Default")
      (node (ref "R23") (pin "2") (pinfunction "2_2") (pintype "passive"))
      (node (ref "R24") (pin "1") (pinfunction "1_1") (pintype "passive"))
    )
    (net (code "12") (name "Net-(R25-Pad2)") (class "Default")
      (node (ref "R25") (pin "2") (pinfunction "2_2") (pintype "passive"))
      (node (ref "R26") (pin "1") (pinfunction "1_1") (pintype "passive"))
    )
    (net (code "13") (name "Net-(R28-Pad2)") (class "Default")
      (node (ref "R28") (pin "2") (pinfunction "2_2") (pintype "passive"))
      (node (ref "R29") (pin "1") (pinfunction "1_1") (pintype "passive"))
    )
    (net (code "14") (name "Net-(R30-Pad2)") (class "Default")
      (node (ref "R30") (pin "2") (pinfunction "2_2") (pintype "passive"))
      (node (ref "R31") (pin "1") (pinfunction "1_1") (pintype "passive"))
    )
    (net (code "15") (name "Net-(R32-Pad2)") (class "Default")
      (node (ref "R32") (pin "2") (pinfunction "2_2") (pintype "passive"))
      (node (ref "R33") (pin "1") (pinfunction "1_1") (pintype "passive"))
    )
    (net (code "16") (name "Net-(R34-Pad2)") (class "Default")
      (node (ref "R34") (pin "2") (pinfunction "2_2") (pintype "passive"))
      (node (ref "R35") (pin "1") (pinfunction "1_1") (pintype "passive"))
    )
    (net (code "17") (name "Net-(R37-Pad2)") (class "Default")
      (node (ref "R37") (pin "2") (pinfunction "2_2") (pintype "passive"))
      (node (ref "R38") (pin "1") (pinfunction "1_1") (pintype "passive"))
    )
    (net (code "18") (name "Net-(R39-Pad2)") (class "Default")
      (node (ref "R39") (pin "2") (pinfunction "2_2") (pintype "passive"))
      (node (ref "R40") (pin "1") (pinfunction "1_1") (pintype "passive"))
    )
    (net (code "19") (name "Net-(R41-Pad2)") (class "Default")
      (node (ref "R41") (pin "2") (pinfunction "2_2") (pintype "passive"))
      (node (ref "R42") (pin "1") (pinfunction "1_1") (pintype "passive"))
    )
    (net (code "20") (name "Net-(R44-Pad2)") (class "Default")
      (node (ref "R44") (pin "2") (pinfunction "2_2") (pintype "passive"))
      (node (ref "R45") (pin "1") (pinfunction "1_1") (pintype "passive"))
    )
    (net (code "21") (name "Net-(R46-Pad2)") (class "Default")
      (node (ref "R46") (pin "2") (pinfunction "2_2") (pintype "passive"))
      (node (ref "R47") (pin "1") (pinfunction "1_1") (pintype "passive"))
    )
    (net (code "22") (name "Net-(R48-Pad2)") (class "Default")
      (node (ref "R48") (pin "2") (pinfunction "2_2") (pintype "passive"))
      (node (ref "R49") (pin "1") (pinfunction "1_1") (pintype "passive"))
    )
    (net (code "23") (name "Net-(R51-Pad2)") (class "Default")
      (node (ref "R51") (pin "2") (pinfunction "2_2") (pintype "passive"))
      (node (ref "R52") (pin "1") (pinfunction "1_1") (pintype "passive"))
    )
    (net (code "24") (name "Net-(R53-Pad2)") (class "Default")
      (node (ref "R53") (pin "2") (pinfunction "2_2") (pintype "passive"))
      (node (ref "R54") (pin "1") (pinfunction "1_1") (pintype "passive"))
    )
    (net (code "25") (name "Net-(R55-Pad2)") (class "Default")
      (node (ref "R55") (pin "2") (pinfunction "2_2") (pintype "passive"))
      (node (ref "R56") (pin "1") (pinfunction "1_1") (pintype "passive"))
    )
    (net (code "26") (name "Net-(R57-Pad2)") (class "Default")
      (node (ref "R57") (pin "2") (pinfunction "2_2") (pintype "passive"))
      (node (ref "R58") (pin "1") (pinfunction "1_1") (pintype "passive"))
    )
    (net (code "27") (name "Net-(R60-Pad2)") (class "Default")
      (node (ref "R60") (pin "2") (pinfunction "2_2") (pintype "passive"))
      (node (ref "R61") (pin "1") (pinfunction "1_1") (pintype "passive"))
    )
    (net (code "28") (name "Net-(R62-Pad2)") (class "Default")
      (node (ref "R62") (pin "2") (pinfunction "2_2") (pintype "passive"))
      (node (ref "R63") (pin "1") (pinfunction "1_1") (pintype "passive"))
    )
    (net (code "29") (name "Net-(R64-Pad2)") (class "Default")
      (node (ref "R64") (pin "2") (pinfunction "2_2") (pintype "passive"))
      (node (ref "R65") (pin "1") (pinfunction "1_1") (pintype "passive"))
    )
    (net (code "30") (name "Net-(R67-Pad2)") (class "Default")
      (node (ref "R67") (pin "2") (pinfunction "2_2") (pintype "passive"))
      (node (ref "R68") (pin "1") (pinfunction "1_1") (pintype "passive"))
    )
    (net (code "31") (name "Net-(R70-Pad2)") (class "Default")
      (node (ref "R70") (pin "2") (pinfunction "2_2") (pintype "passive"))
      (node (ref "R71") (pin "1") (pinfunction "1_1") (pintype "passive"))
    )
    (net (code "32") (name "Net-(R72-Pad2)") (class "Default")
      (node (ref "R72") (pin "2") (pinfunction "2_2") (pintype "passive"))
      (node (ref "R73") (pin "1") (pinfunction "1_1") (pintype "passive"))
    )
    (net (code "33") (name "Net-(R74-Pad2)") (class "Default")
      (node (ref "R74") (pin "2") (pinfunction "2_2") (pintype "passive"))
      (node (ref "R75") (pin "1") (pinfunction "1_1") (pintype "passive"))
    )
    (net (code "34") (name "Net-(R76-Pad2)") (class "Default")
      (node (ref "R76") (pin "2") (pinfunction "2_2") (pintype "passive"))
      (node (ref "R77") (pin "1") (pinfunction "1_1") (pintype "passive"))
    )
    (net (code "35") (name "Net-(R79-Pad2)") (class "Default")
      (node (ref "R79") (pin "2") (pinfunction "2_2") (pintype "passive"))
      (node (ref "R80") (pin "1") (pinfunction "1_1") (pintype "passive"))
    )
    (net (code "36") (name "Net-(R82-Pad2)") (class "Default")
      (node (ref "R82") (pin "2") (pinfunction "2_2") (pintype "passive"))
      (node (ref "R83") (pin "1") (pinfunction "1_1") (pintype "passive"))
    )
    (net (code "37") (name "Net-(R84-Pad2)") (class "Default")
      (node (ref "R84") (pin "2") (pinfunction "2_2") (pintype "passive"))
      (node (ref "R85") (pin "1") (pinfunction "1_1") (pintype "passive"))
    )
    (net (code "38") (name "Net-(R86-Pad2)") (class "Default")
      (node (ref "R86") (pin "2") (pinfunction "2_2") (pintype "passive"))
      (node (ref "R87") (pin "1") (pinfunction "1_1") (pintype "passive"))
    )
    (net (code "39") (name "Net-(R88-Pad2)") (class "Default")
      (node (ref "R88") (pin "2") (pinfunction "2_2") (pintype "passive"))
      (node (ref "R89") (pin "1") (pinfunction "1_1") (pintype "passive"))
    )
    (net (code "40") (name "Net-(R91-Pad2)") (class "Default")
      (node (ref "R91") (pin "2") (pinfunction "2_2") (pintype "passive"))
      (node (ref "R92") (pin "1") (pinfunction "1_1") (pintype "passive"))
    )
    (net (code "41") (name "Net-(R93-Pad2)") (class "Default")
      (node (ref "R93") (pin "2") (pinfunction "2_2") (pintype "passive"))
      (node (ref "R94") (pin "1") (pinfunction "1_1") (pintype "passive"))
    )
    (net (code "42") (name "Net-(R95-Pad2)") (class "Default")
      (node (ref "R95") (pin "2") (pinfunction "2_2") (pintype "passive"))
      (node (ref "R96") (pin "1") (pinfunction "1_1") (pintype "passive"))
    )
    (net (code "43") (name "Net-(R98-Pad2)") (class "Default")
      (node (ref "R98") (pin "2") (pinfunction "2_2") (pintype "passive"))
      (node (ref "R99") (pin "1") (pinfunction "1_1") (pintype "passive"))
    )
    (net (code "44") (name "Net-(R100-Pad2)") (class "Default")
      (node (ref "R100") (pin "2") (pinfunction "2_2") (pintype "passive"))
      (node (ref "R101") (pin "1") (pinfunction "1_1") (pintype "passive"))
    )
    (net (code "45") (name "Net-(R102-Pad2)") (class "Default")
      (node (ref "R102") (pin "2") (pinfunction "2_2") (pintype "passive"))
      (node (ref "R103") (pin "1") (pinfunction "1_1") (pintype "passive"))
    )
    (net (code "46") (name "Net-(R105-Pad2)") (class "Default")
      (node (ref "R105") (pin "2") (pinfunction "2_2") (pintype "passive"))
      (node (ref "R106") (pin "1") (pinfunction "1_1") (pintype "passive"))
    )
    (net (code "47") (name "Net-(R107-Pad2)") (class "Default")
      (node (ref "R107") (pin "2") (pinfunction "2_2") (pintype "passive"))
      (node (ref "R108") (pin "1") (pinfunction "1_1") (pintype "passive"))
    )
    (net (code "48") (name "Net-(R109-Pad2)") (class "Default")
      (node (ref "R109") (pin "2") (pinfunction "2_2") (pintype "passive"))
      (node (ref "R110") (pin "1") (pinfunction "1_1") (pintype "passive"))
    )
    (net (code "49") (name "Net-(R111-Pad2)") (class "Default")
      (node (ref "R111") (pin "2") (pinfunction "2_2") (pintype "passive"))
      (node (ref "R112") (pin "1") (pinfunction "1_1") (pintype "passive"))
    )
    (net (code "50") (name "Net-(R114-Pad2)") (class "Default")
      (node (ref "R114") (pin "2") (pinfunction "2_2") (pintype "passive"))
      (node (ref "R115") (pin "1") (pinfunction "1_1") (pintype "passive"))
    )
    (net (code "51") (name "Net-(R116-Pad2)") (class "Default")
      (node (ref "R116") (pin "2") (pinfunction "2_2") (pintype "passive"))
      (node (ref "R117") (pin "1") (pinfunction "1_1") (pintype "passive"))
    )
    (net (code "52") (name "Net-(R118-Pad2)") (class "Default")
      (node (ref "R118") (pin "2") (pinfunction "2_2") (pintype "passive"))
      (node (ref "R119") (pin "1") (pinfunction "1_1") (pintype "passive"))
    )
    (net (code "53") (name "Net-(R121-Pad2)") (class "Default")
      (node (ref "R121") (pin "2") (pinfunction "2_2") (pintype "passive"))
      (node (ref "R122") (pin "1") (pinfunction "1_1") (pintype "passive"))
    )
    (net (code "54") (name "Net-(R123-Pad2)") (class "Default")
      (node (ref "R123") (pin "2") (pinfunction "2_2") (pintype "passive"))
      (node (ref "R124") (pin "1") (pinfunction "1_1") (pintype "passive"))
    )
    (net (code "55") (name "Net-(R125-Pad2)") (class "Default")
      (node (ref "R125") (pin "2") (pinfunction "2_2") (pintype "passive"))
      (node (ref "R126") (pin "1") (pinfunction "1_1") (pintype "passive"))
    )
    (net (code "56") (name "Net-(R128-Pad2)") (class "Default")
      (node (ref "R128") (pin "2") (pinfunction "2_2") (pintype "passive"))
      (node (ref "R129") (pin "1") (pinfunction "1_1") (pintype "passive"))
    )
    (net (code "57") (name "Net-(R130-Pad2)") (class "Default")
      (node (ref "R130") (pin "2") (pinfunction "2_2") (pintype "passive"))
      (node (ref "R131") (pin "1") (pinfunction "1_1") (pintype "passive"))
    )
    (net (code "58") (name "Net-(R132-Pad2)") (class "Default")
      (node (ref "R132") (pin "2") (pinfunction "2_2") (pintype "passive"))
      (node (ref "R133") (pin "1") (pinfunction "1_1") (pintype "passive"))
    )
    (net (code "59") (name "Net-(R134-Pad2)") (class "Default")
      (node (ref "R134") (pin "2") (pinfunction "2_2") (pintype "passive"))
      (node (ref "R135") (pin "1") (pinfunction "1_1") (pintype "passive"))
    )
    (net (code "60") (name "Net-(R137-Pad2)") (class "Default")
      (node (ref "R137") (pin "2") (pinfunction "2_2") (pintype "passive"))
      (node (ref "R138") (pin "1") (pinfunction "1_1") (pintype "passive"))
    )
    (net (code "61") (name "Net-(R139-Pad2)") (class "Default")
      (node (ref "R139") (pin "2") (pinfunction "2_2") (pintype "passive"))
      (node (ref "R140") (pin "1") (pinfunction "1_1") (pintype "passive"))
    )
    (net (code "62") (name "Net-(R141-Pad2)") (class "Default")
      (node (ref "R141") (pin "2") (pinfunction "2_2") (pintype "passive"))
      (node (ref "R142") (pin "1") (pinfunction "1_1") (pintype "passive"))
    )
    (net (code "63") (name "Net-(R144-Pad2)") (class "Default")
      (node (ref "R144") (pin "2") (pinfunction "2_2") (pintype "passive"))
      (node (ref "R145") (pin "1") (pinfunction "1_1") (pintype "passive"))
    )
    (net (code "64") (name "Net-(R146-Pad2)") (class "Default")
      (node (ref "R146") (pin "2") (pinfunction "2_2") (pintype "passive"))
      (node (ref "R147") (pin "1") (pinfunction "1_1") (pintype "passive"))
    )
    (net (code "65") (name "Net-(R148-Pad2)") (class "Default")
      (node (ref "R148") (pin "2") (pinfunction "2_2") (pintype "passive"))
      (node (ref "R149") (pin "1") (pinfunction "1_1") (pintype "passive"))
    )
    (net (code "66") (name "Net-(R151-Pad2)") (class "Default")
      (node (ref "R151") (pin "2") (pinfunction "2_2") (pintype "passive"))
      (node (ref "R152") (pin "1") (pinfunction "1_1") (pintype "passive"))
    )
    (net (code "67") (name "Net-(R153-Pad2)") (class "Default")
      (node (ref "R153") (pin "2") (pinfunction "2_2") (pintype "passive"))
      (node (ref "R154") (pin "1") (pinfunction "1_1") (pintype "passive"))
    )
    (net (code "68") (name "Net-(R155-Pad2)") (class "Default")
      (node (ref "R155") (pin "2") (pinfunction "2_2") (pintype "passive"))
      (node (ref "R156") (pin "1") (pinfunction "1_1") (pintype "passive"))
    )
    (net (code "69") (name "Net-(R157-Pad2)") (class "Default")
      (node (ref "R157") (pin "2") (pinfunction "2_2") (pintype "passive"))
      (node (ref "R158") (pin "1") (pinfunction "1_1") (pintype "passive"))
    )
    (net (code "70") (name "Net-(R159-Pad2)") (class "Default")
      (node (ref "R159") (pin "2") (pinfunction "2_2") (pintype "passive"))
      (node (ref "R160") (pin "1") (pinfunction "1_1") (pintype "passive"))
    )
    (net (code "71") (name "Net-(R162-Pad2)") (class "Default")
      (node (ref "R162") (pin "2") (pinfunction "2_2") (pintype "passive"))
      (node (ref "R163") (pin "1") (pinfunction "1_1") (pintype "passive"))
    )
    (net (code "72") (name "Net-(R164-Pad2)") (class "Default")
      (node (ref "R164") (pin "2") (pinfunction "2_2") (pintype "passive"))
      (node (ref "R165") (pin "1") (pinfunction "1_1") (pintype "passive"))
    )
    (net (code "73") (name "Net-(R166-Pad2)") (class "Default")
      (node (ref "R166") (pin "2") (pinfunction "2_2") (pintype "passive"))
      (node (ref "R167") (pin "1") (pinfunction "1_1") (pintype "passive"))
    )
    (net (code "74") (name "Net-(R168-Pad2)") (class "Default")
      (node (ref "R168") (pin "2") (pinfunction "2_2") (pintype "passive"))
      (node (ref "R169") (pin "1") (pinfunction "1_1") (pintype "passive"))
    )
    (net (code "75") (name "Net-(R171-Pad2)") (class "Default")
      (node (ref "R171") (pin "2") (pinfunction "2_2") (pintype "passive"))
      (node (ref "R172") (pin "1") (pinfunction "1_1") (pintype "passive"))
    )
    (net (code "76") (name "Net-(R173-Pad2)") (class "Default")
      (node (ref "R173") (pin "2") (pinfunction "2_2") (pintype "passive"))
      (node (ref "R174") (pin "1") (pinfunction "1_1") (pintype "passive"))
    )
    (net (code "77") (name "Net-(R175-Pad2)") (class "Default")
      (node (ref "R175") (pin "2") (pinfunction "2_2") (pintype "passive"))
      (node (ref "R176") (pin "1") (pinfunction "1_1") (pintype "passive"))
    )
    (net (code "78") (name "Net-(R178-Pad2)") (class "Default")
      (node (ref "R178") (pin "2") (pinfunction "2_2") (pintype "passive"))
      (node (ref "R179") (pin "1") (pinfunction "1_1") (pintype "passive"))
    )
    (net (code "79") (name "Net-(R180-Pad2)") (class "Default")
      (node (ref "R180") (pin "2") (pinfunction "2_2") (pintype "passive"))
      (node (ref "R181") (pin "1") (pinfunction "1_1") (pintype "passive"))
    )
    (net (code "80") (name "Net-(R182-Pad2)") (class "Default")
      (node (ref "R182") (pin "2") (pinfunction "2_2") (pintype "passive"))
      (node (ref "R183") (pin "1") (pinfunction "1_1") (pintype "passive"))
    )
    (net (code "81") (name "Net-(R185-Pad2)") (class "Default")
      (node (ref "R185") (pin "2") (pinfunction "2_2") (pintype "passive"))
      (node (ref "R186") (pin "1") (pinfunction "1_1") (pintype "passive"))
    )
    (net (code "82") (name "Net-(R187-Pad2)") (class "Default")
      (node (ref "R187") (pin "2") (pinfunction "2_2") (pintype "passive"))
      (node (ref "R188") (pin "1") (pinfunction "1_1") (pintype "passive"))
    )
    (net (code "83") (name "Net-(R189-Pad2)") (class "Default")
      (node (ref "R189") (pin "2") (pinfunction "2_2") (pintype "passive"))
      (node (ref "R190") (pin "1") (pinfunction "1_1") (pintype "passive"))
    )
    (net (code "84") (name "unconnected-(D1-A-Pad1)") (class "Default")
      (node (ref "D1") (pin "1") (pinfunction "A_1") (pintype "passive"))
    )
    (net (code "85") (name "unconnected-(D2-K-Pad2)") (class "Default")
      (node (ref "D2") (pin "2") (pinfunction "K_2") (pintype "passive"))
    )
    (net (code "86") (name "unconnected-(Q1-B-Pad1)") (class "Default")
      (node (ref "Q1") (pin "1") (pinfunction "B_1") (pintype "passive"))
    )
    (net (code "87") (name "unconnected-(Q1-C-Pad3)") (class "Default")
      (node (ref "Q1") (pin "3") (pinfunction "C_3") (pintype "passive"))
    )
    (net (code "88") (name "unconnected-(Q1-E-Pad2)") (class "Default")
      (node (ref "Q1") (pin "2") (pinfunction "E_2") (pintype "passive"))
    )
    (net (code "89") (name "unconnected-(Q2-B-Pad1)") (class "Default")
      (node (ref "Q2") (pin "1") (pinfunction "B_1") (pintype "passive"))
    )
    (net (code "90") (name "unconnected-(Q2-C-Pad3)") (class "Default")
      (node (ref "Q2") (pin "3") (pinfunction "C_3") (pintype "passive"))
    )
    (net (code "91") (name "unconnected-(Q2-E-Pad2)") (class "Default")
      (node (ref "Q2") (pin "2") (pinfunction "E_2") (pintype "passive"))
    )
    (net (code "92") (name "unconnected-(Q3-B-Pad1)") (class "Default")
      (node (ref "Q3") (pin "1") (pinfunction "B_1") (pintype "passive"))
    )
    (net (code "93") (name "unconnected-(Q3-C-Pad3)") (class "Default")
      (node (ref "Q3") (pin "3") (pinfunction "C_3") (pintype "passive"))
    )
    (net (code "94") (name "unconnected-(Q3-E-Pad2)") (class "Default")
      (node (ref "Q3") (pin "2") (pinfunction "E_2") (pintype "passive"))
    )
    (net (code "95") (name "unconnected-(Q4-B-Pad1)") (class "Default")
      (node (ref "Q4") (pin "1") (pinfunction "B_1") (pintype "passive"))
    )
    (net (code "96") (name "unconnected-(Q4-C-Pad2)") (class "Default")
      (node (ref "Q4") (pin "2") (pinfunction "C_2") (pintype "passive"))
    )
    (net (code "97") (name "unconnected-(Q4-E-Pad3)") (class "Default")
      (node (ref "Q4") (pin "3") (pinfunction "E_3") (pintype "passive"))
    )
    (net (code "98") (name "unconnected-(Q5-B-Pad1)") (class "Default")
      (node (ref "Q5") (pin "1") (pinfunction "B_1") (pintype "passive"))
    )
    (net (code "99") (name "unconnected-(Q5-C-Pad3)") (class "Default")
      (node (ref "Q5") (pin "3") (pinfunction "C_3") (pintype "passive"))
    )
    (net (code "100") (name "unconnected-(Q5-E-Pad2)") (class "Default")
      (node (ref "Q5") (pin "2") (pinfunction "E_2") (pintype "passive"))
    )
    (net (code "101") (name "unconnected-(Q6-B-Pad1)") (class "Default")
      (node (ref "Q6") (pin "1") (pinfunction "B_1") (pintype "passive"))
    )
    (net (code "102") (name "unconnected-(Q6-C-Pad3)") (class "Default")
      (node (ref "Q6") (pin "3") (pinfunction "C_3") (pintype "passive"))
    )
    (net (code "103") (name "unconnected-(Q6-E-Pad2)") (class "Default")
      (node (ref "Q6") (pin "2") (pinfunction "E_2") (pintype "passive"))
    )
    (net (code "104") (name "unconnected-(Q7-B-Pad1)") (class "Default")
      (node (ref "Q7") (pin "1") (pinfunction "B_1") (pintype "passive"))
    )
    (net (code "105") (name "unconnected-(Q7-C-Pad2)") (class "Default")
      (node (ref "Q7") (pin "2") (pinfunction "C_2") (pintype "passive"))
    )
    (net (code "106") (name "unconnected-(Q7-E-Pad3)") (class "Default")
      (node (ref "Q7") (pin "3") (pinfunction "E_3") (pintype "passive"))
    )
    (net (code "107") (name "unconnected-(R1-Pad1)") (class "Default")
      (node (ref "R1") (pin "1") (pinfunction "1_1") (pintype "passive"))
    )
    (net (code "108") (name "unconnected-(R1-Pad2)") (class "Default")
      (node (ref "R1") (pin "2") (pinfunction "2_2") (pintype "passive"))
    )
    (net (code "109") (name "unconnected-(R1-Pad3)") (class "Default")
      (node (ref "R1") (pin "3") (pinfunction "3_3") (pintype "passive"))
    )
    (net (code "110") (name "unconnected-(R1-Pad4)") (class "Default")
      (node (ref "R1") (pin "4") (pinfunction "4_4") (pintype "passive"))
    )
    (net (code "111") (name "unconnected-(R1-Pad5)") (class "Default")
      (node (ref "R1") (pin "5") (pinfunction "5_5") (pintype "passive"))
    )
    (net (code "112") (name "unconnected-(R1-Pad6)") (class "Default")
      (node (ref "R1") (pin "6") (pinfunction "6_6") (pintype "passive"))
    )
    (net (code "113") (name "unconnected-(R1-Pad7)") (class "Default")
      (node (ref "R1") (pin "7") (pinfunction "7_7") (pintype "passive"))
    )
    (net (code "114") (name "unconnected-(R1-Pad8)") (class "Default")
      (node (ref "R1") (pin "8") (pinfunction "8_8") (pintype "passive"))
    )
    (net (code "115") (name "unconnected-(R2-Pad1)") (class "Default")
      (node (ref "R2") (pin "1") (pinfunction "1_1") (pintype "passive"))
    )
    (net (code "116") (name "unconnected-(R2-Pad2)") (class "Default")
      (node (ref "R2") (pin "2") (pinfunction "2_2") (pintype "passive"))
    )
    (net (code "117") (name "unconnected-(R2-Pad3)") (class "Default")
      (node (ref "R2") (pin "3") (pinfunction "3_3") (pintype "passive"))
    )
    (net (code "118") (name "unconnected-(R2-Pad4)") (class "Default")
      (node (ref "R2") (pin "4") (pinfunction "4_4") (pintype "passive"))
    )
    (net (code "119") (name "unconnected-(R2-Pad5)") (class "Default")
      (node (ref "R2") (pin "5") (pinfunction "5_5") (pintype "passive"))
    )
    (net (code "120") (name "unconnected-(R2-Pad6)") (class "Default")
      (node (ref "R2") (pin "6") (pinfunction "6_6") (pintype "passive"))
    )
    (net (code "121") (name "unconnected-(R2-Pad7)") (class "Default")
      (node (ref "R2") (pin "7") (pinfunction "7_7") (pintype "passive"))
    )
    (net (code "122") (name "unconnected-(R2-Pad8)") (class "Default")
      (node (ref "R2") (pin "8") (pinfunction "8_8") (pintype "passive"))
    )
    (net (code "123") (name "unconnected-(R3-Pad1)") (class "Default")
      (node (ref "R3") (pin "1") (pinfunction "1_1") (pintype "passive"))
    )
    (net (code "124") (name "unconnected-(R3-Pad2)") (class "Default")
      (node (ref "R3") (pin "2") (pinfunction "2_2") (pintype "passive"))
    )
    (net (code "125") (name "unconnected-(R3-Pad3)") (class "Default")
      (node (ref "R3") (pin "3") (pinfunction "3_3") (pintype "passive"))
    )
    (net (code "126") (name "unconnected-(R3-Pad4)") (class "Default")
      (node (ref "R3") (pin "4") (pinfunction "4_4") (pintype "passive"))
    )
    (net (code "127") (name "unconnected-(R3-Pad5)") (class "Default")
      (node (ref "R3") (pin "5") (pinfunction "5_5") (pintype "passive"))
    )
    (net (code "128") (name "unconnected-(R3-Pad6)") (class "Default")
      (node (ref "R3") (pin "6") (pinfunction "6_6") (pintype "passive"))
    )
    (net (code "129") (name "unconnected-(R3-Pad7)") (class "Default")
      (node (ref "R3") (pin "7") (pinfunction "7_7") (pintype "passive"))
    )
    (net (code "130") (name "unconnected-(R3-Pad8)") (class "Default")
      (node (ref "R3") (pin "8") (pinfunction "8_8") (pintype "passive"))
    )
    (net (code "131") (name "unconnected-(R4-Pad1)") (class "Default")
      (node (ref "R4") (pin "1") (pinfunction "1_1") (pintype "passive"))
    )
    (net (code "132") (name "unconnected-(R4-Pad2)") (class "Default")
      (node (ref "R4") (pin "2") (pinfunction "2_2") (pintype "passive"))
    )
    (net (code "133") (name "unconnected-(R4-Pad3)") (class "Default")
      (node (ref "R4") (pin "3") (pinfunction "3_3") (pintype "passive"))
    )
    (net (code "134") (name "unconnected-(R4-Pad4)") (class "Default")
      (node (ref "R4") (pin "4") (pinfunction "4_4") (pintype "passive"))
    )
    (net (code "135") (name "unconnected-(R4-Pad5)") (class "Default")
      (node (ref "R4") (pin "5") (pinfunction "5_5") (pintype "passive"))
    )
    (net (code "136") (name "unconnected-(R4-Pad6)") (class "Default")
      (node (ref "R4") (pin "6") (pinfunction "6_6") (pintype "passive"))
    )
    (net (code "137") (name "unconnected-(R4-Pad7)") (class "Default")
      (node (ref "R4") (pin "7") (pinfunction "7_7") (pintype "passive"))
    )
    (net (code "138") (name "unconnected-(R5-Pad1)") (class "Default")
      (node (ref "R5") (pin "1") (pinfunction "1_1") (pintype "passive"))
    )
    (net (code "139") (name "unconnected-(R6-Pad2)") (class "Default")
      (node (ref "R6") (pin "2") (pinfunction "2_2") (pintype "passive"))
    )
    (net (code "140") (name "unconnected-(R7-Pad1)") (class "Default")
      (node (ref "R7") (pin "1") (pinfunction "1_1") (pintype "passive"))
    )
    (net (code "141") (name "unconnected-(R8-Pad2)") (class "Default")
      (node (ref "R8") (pin "2") (pinfunction "2_2") (pintype "passive"))
    )
    (net (code "142") (name "unconnected-(R9-Pad1)") (class "Default")
      (node (ref "R9") (pin "1") (pinfunction "1_1") (pintype "passive"))
    )
    (net (code "143") (name "unconnected-(R10-Pad2)") (class "Default")
      (node (ref "R10") (pin "2") (pinfunction "2_2") (pintype "passive"))
    )
    (net (code "144") (name "unconnected-(R11-Pad1)") (class "Default")
      (node (ref "R11") (pin "1") (pinfunction "1_1") (pintype "passive"))
    )
    (net (code "145") (name "unconnected-(R12-Pad2)") (class "Default")
      (node (ref "R12") (pin "2") (pinfunction "2_2") (pintype "passive"))
    )
    (net (code "146") (name "unconnected-(R13-Pad1)") (class "Default")
      (node (ref "R13") (pin "1") (pinfunction "1_1") (pintype "passive"))
    )
    (net (code "147") (name "unconnected-(R13-Pad2)") (class "Default")
      (node (ref "R13") (pin "2") (pinfunction "2_2") (pintype "passive"))
    )
    (net (code "148") (name "unconnected-(R14-Pad1)") (class "Default")
      (node (ref "R14") (pin "1") (pinfunction "1_1") (pintype "passive"))
    )
    (net (code "149") (name "unconnected-(R15-Pad2)") (class "Default")
      (node (ref "R15") (pin "2") (pinfunction "2_2") (pintype "passive"))
    )
    (net (code "150") (name "unconnected-(R16-Pad1)") (class "Default")
      (node (ref "R16") (pin "1") (pinfunction "1_1") (pintype "passive"))
    )
    (net (code "151") (name "unconnected-(R17-Pad2)") (class "Default")
      (node (ref "R17") (pin "2") (pinfunction "2_2") (pintype "passive"))
    )
    (net (code "152") (name "unconnected-(R18-Pad1)") (class "Default")
      (node (ref "R18") (pin "1") (pinfunction "1_1") (pintype "passive"))
    )
    (net (code "153") (name "unconnected-(R19-Pad2)") (class "Default")
      (node (ref "R19") (pin "2") (pinfunction "2_2") (pintype "passive"))
    )
    (net (code "154") (name "unconnected-(R20-Pad1)") (class "Default")
      (node (ref "R20") (pin "1") (pinfunction "1_1") (pintype "passive"))
    )
    (net (code "155") (name "unconnected-(R20-Pad2)") (class "Default")
      (node (ref "R20") (pin "2") (pinfunction "2_2") (pintype "passive"))
    )
    (net (code "156") (name "unconnected-(R21-Pad1)") (class "Default")
      (node (ref "R21") (pin "1") (pinfunction "1_1") (pintype "passive"))
    )
    (net (code "157") (name "unconnected-(R22-Pad2)") (class "Default")
      (node (ref "R22") (pin "2") (pinfunction "2_2") (pintype "passive"))
    )
    (net (code "158") (name "unconnected-(R23-Pad1)") (class "Default")
      (node (ref "R23") (pin "1") (pinfunction "1_1") (pintype "passive"))
    )
    (net (code "159") (name "unconnected-(R24-Pad2)") (class "Default")
      (node (ref "R24") (pin "2") (pinfunction "2_2") (pintype "passive"))
    )
    (net (code "160") (name "unconnected-(R25-Pad1)") (class "Default")
      (node (ref "R25") (pin "1") (pinfunction "1_1") (pintype "passive"))
    )
    (net (code "161") (name "unconnected-(R26-Pad2)") (class "Default")
      (node (ref "R26") (pin "2") (pinfunction "2_2") (pintype "passive"))
    )
    (net (code "162") (name "unconnected-(R27-Pad1)") (class "Default")
      (node (ref "R27") (pin "1") (pinfunction "1_1") (pintype "passive"))
    )
    (net (code "163") (name "unconnected-(R27-Pad2)") (class "Default")
      (node (ref "R27") (pin "2") (pinfunction "2_2") (pintype "passive"))
    )
    (net (code "164") (name "unconnected-(R28-Pad1)") (class "Default")
      (node (ref "R28") (pin "1") (pinfunction "1_1") (pintype "passive"))
    )
    (net (code "165") (name "unconnected-(R29-Pad2)") (class "Default")
      (node (ref "R29") (pin "2") (pinfunction "2_2") (pintype "passive"))
    )
    (net (code "166") (name "unconnected-(R30-Pad1)") (class "Default")
      (node (ref "R30") (pin "1") (pinfunction "1_1") (pintype "passive"))
    )
    (net (code "167") (name "unconnected-(R31-Pad2)") (class "Default")
      (node (ref "R31") (pin "2") (pinfunction "2_2") (pintype "passive"))
    )
    (net (code "168") (name "unconnected-(R32-Pad1)") (class "Default")
      (node (ref "R32") (pin "1") (pinfunction "1_1") (pintype "passive"))
    )
    (net (code "169") (name "unconnected-(R33-Pad2)") (class "Default")
      (node (ref "R33") (pin "2") (pinfunction "2_2") (pintype "passive"))
    )
    (net (code "170") (name "unconnected-(R34-Pad1)") (class "Default")
      (node (ref "R34") (pin "1") (pinfunction "1_1") (pintype "passive"))
    )
    (net (code "171") (name "unconnected-(R35-Pad2)") (class "Default")
      (node (ref "R35") (pin "2") (pinfunction "2_2") (pintype "passive"))
    )
    (net (code "172") (name "unconnected-(R36-Pad1)") (class "Default")
      (node (ref "R36") (pin "1") (pinfunction "1_1") (pintype "passive"))
    )
    (net (code "173") (name "unconnected-(R36-Pad2)") (class "Default")
      (node (ref "R36") (pin "2") (pinfunction "2_2") (pintype "passive"))
    )
    (net (code "174") (name "unconnected-(R37-Pad1)") (class "Default")
      (node (ref "R37") (pin "1") (pinfunction "1_1") (pintype "passive"))
    )
    (net (code "175") (name "unconnected-(R38-Pad2)") (class "Default")
      (node (ref "R38") (pin "2") (pinfunction "2_2") (pintype "passive"))
    )
    (net (code "176") (name "unconnected-(R39-Pad1)") (class "Default")
      (node (ref "R39") (pin "1") (pinfunction "1_1") (pintype "passive"))
    )
    (net (code "177") (name "unconnected-(R40-Pad2)") (class "Default")
      (node (ref "R40") (pin "2") (pinfunction "2_2") (pintype "passive"))
    )
    (net (code "178") (name "unconnected-(R41-Pad1)") (class "Default")
      (node (ref "R41") (pin "1") (pinfunction "1_1") (pintype "passive"))
    )
    (net (code "179") (name "unconnected-(R42-Pad2)") (class "Default")
      (node (ref "R42") (pin "2") (pinfunction "2_2") (pintype "passive"))
    )
    (net (code "180") (name "unconnected-(R43-Pad1)") (class "Default")
      (node (ref "R43") (pin "1") (pinfunction "1_1") (pintype "passive"))
    )
    (net (code "181") (name "unconnected-(R43-Pad2)") (class "Default")
      (node (ref "R43") (pin "2") (pinfunction "2_2") (pintype "passive"))
    )
    (net (code "182") (name "unconnected-(R44-Pad1)") (class "Default")
      (node (ref "R44") (pin "1") (pinfunction "1_1") (pintype "passive"))
    )
    (net (code "183") (name "unconnected-(R45-Pad2)") (class "Default")
      (node (ref "R45") (pin "2") (pinfunction "2_2") (pintype "passive"))
    )
    (net (code "184") (name "unconnected-(R46-Pad1)") (class "Default")
      (node (ref "R46") (pin "1") (pinfunction "1_1") (pintype "passive"))
    )
    (net (code "185") (name "unconnected-(R47-Pad2)") (class "Default")
      (node (ref "R47") (pin "2") (pinfunction "2_2") (pintype "passive"))
    )
    (net (code "186") (name "unconnected-(R48-Pad1)") (class "Default")
      (node (ref "R48") (pin "1") (pinfunction "1_1") (pintype "passive"))
    )
    (net (code "187") (name "unconnected-(R49-Pad2)") (class "Default")
      (node (ref "R49") (pin "2") (pinfunction "2_2") (pintype "passive"))
    )
    (net (code "188") (name "unconnected-(R50-Pad1)") (class "Default")
      (node (ref "R50") (pin "1") (pinfunction "1_1") (pintype "passive"))
    )
    (net (code "189") (name "unconnected-(R50-Pad2)") (class "Default")
      (node (ref "R50") (pin "2") (pinfunction "2_2") (pintype "passive"))
    )
    (net (code "190") (name "unconnected-(R51-Pad1)") (class "Default")
      (node (ref "R51") (pin "1") (pinfunction "1_1") (pintype "passive"))
    )
    (net (code "191") (name "unconnected-(R52-Pad2)") (class "Default")
      (node (ref "R52") (pin "2") (pinfunction "2_2") (pintype "passive"))
    )
    (net (code "192") (name "unconnected-(R53-Pad1)") (class "Default")
      (node (ref "R53") (pin "1") (pinfunction "1_1") (pintype "passive"))
    )
    (net (code "193") (name "unconnected-(R54-Pad2)") (class "Default")
      (node (ref "R54") (pin "2") (pinfunction "2_2") (pintype "passive"))
    )
    (net (code "194") (name "unconnected-(R55-Pad1)") (class "Default")
      (node (ref "R55") (pin "1") (pinfunction "1_1") (pintype "passive"))
    )
    (net (code "195") (name "unconnected-(R56-Pad2)") (class "Default")
      (node (ref "R56") (pin "2") (pinfunction "2_2") (pintype "passive"))
    )
    (net (code "196") (name "unconnected-(R57-Pad1)") (class "Default")
      (node (ref "R57") (pin "1") (pinfunction "1_1") (pintype "passive"))
    )
    (net (code "197") (name "unconnected-(R58-Pad2)") (class "Default")
      (node (ref "R58") (pin "2") (pinfunction "2_2") (pintype "passive"))
    )
    (net (code "198") (name "unconnected-(R59-Pad1)") (class "Default")
      (node (ref "R59") (pin "1") (pinfunction "1_1") (pintype "passive"))
    )
    (net (code "199") (name "unconnected-(R59-Pad2)") (class "Default")
      (node (ref "R59") (pin "2") (pinfunction "2_2") (pintype "passive"))
    )
    (net (code "200") (name "unconnected-(R60-Pad1)") (class "Default")
      (node (ref "R60") (pin "1") (pinfunction "1_1") (pintype "passive"))
    )
    (net (code "201") (name "unconnected-(R61-Pad2)") (class "Default")
      (node (ref "R61") (pin "2") (pinfunction "2_2") (pintype "passive"))
    )
    (net (code "202") (name "unconnected-(R62-Pad1)") (class "Default")
      (node (ref "R62") (pin "1") (pinfunction "1_1") (pintype "passive"))
    )
    (net (code "203") (name "unconnected-(R63-Pad2)") (class "Default")
      (node (ref "R63") (pin "2") (pinfunction "2_2") (pintype "passive"))
    )
    (net (code "204") (name "unconnected-(R64-Pad1)") (class "Default")
      (node (ref "R64") (pin "1") (pinfunction "1_1") (pintype "passive"))
    )
    (net (code "205") (name "unconnected-(R65-Pad2)") (class "Default")
      (node (ref "R65") (pin "2") (pinfunction "2_2") (pintype "passive"))
    )
    (net (code "206") (name "unconnected-(R66-Pad2)") (class "Default")
      (node (ref "R66") (pin "2") (pinfunction "2_2") (pintype "passive"))
    )
    (net (code "207") (name "unconnected-(R67-Pad1)") (class "Default")
      (node (ref "R67") (pin "1") (pinfunction "1_1") (pintype "passive"))
    )
    (net (code "208") (name "unconnected-(R68-Pad2)") (class "Default")
      (node (ref "R68") (pin "2") (pinfunction "2_2") (pintype "passive"))
    )
    (net (code "209") (name "unconnected-(R69-Pad1)") (class "Default")
      (node (ref "R69") (pin "1") (pinfunction "1_1") (pintype "passive"))
    )
    (net (code "210") (name "unconnected-(R69-Pad2)") (class "Default")
      (node (ref "R69") (pin "2") (pinfunction "2_2") (pintype "passive"))
    )
    (net (code "211") (name "unconnected-(R70-Pad1)") (class "Default")
      (node (ref "R70") (pin "1") (pinfunction "1_1") (pintype "passive"))
    )
    (net (code "212") (name "unconnected-(R71-Pad2)") (class "Default")
      (node (ref "R71") (pin "2") (pinfunction "2_2") (pintype "passive"))
    )
    (net (code "213") (name "unconnected-(R72-Pad1)") (class "Default")
      (node (ref "R72") (pin "1") (pinfunction "1_1") (pintype "passive"))
    )
    (net (code "214") (name "unconnected-(R73-Pad2)") (class "Default")
      (node (ref "R73") (pin "2") (pinfunction "2_2") (pintype "passive"))
    )
    (net (code "215") (name "unconnected-(R74-Pad1)") (class "Default")
      (node (ref "R74") (pin "1") (pinfunction "1_1") (pintype "passive"))
    )
    (net (code "216") (name "unconnected-(R75-Pad2)") (class "Default")
      (node (ref "R75") (pin "2") (pinfunction "2_2") (pintype "passive"))
    )
    (net (code "217") (name "unconnected-(R76-Pad1)") (class "Default")
      (node (ref "R76") (pin "1") (pinfunction "1_1") (pintype "passive"))
    )
    (net (code "218") (name "unconnected-(R77-Pad2)") (class "Default")
      (node (ref "R77") (pin "2") (pinfunction "2_2") (pintype "passive"))
    )
    (net (code "219") (name "unconnected-(R78-Pad1)") (class "Default")
      (node (ref "R78") (pin "1") (pinfunction "1_1") (pintype "passive"))
    )
    (net (code "220") (name "unconnected-(R78-Pad2)") (class "Default")
      (node (ref "R78") (pin "2") (pinfunction "2_2") (pintype "passive"))
    )
    (net (code "221") (name "unconnected-(R79-Pad1)") (class "Default")
      (node (ref "R79") (pin "1") (pinfunction "1_1") (pintype "passive"))
    )
    (net (code "222") (name "unconnected-(R80-Pad2)") (class "Default")
      (node (ref "R80") (pin "2") (pinfunction "2_2") (pintype "passive"))
    )
    (net (code "223") (name "unconnected-(R81-Pad1)") (class "Default")
      (node (ref "R81") (pin "1") (pinfunction "1_1") (pintype "passive"))
    )
    (net (code "224") (name "unconnected-(R81-Pad2)") (class "Default")
      (node (ref "R81") (pin "2") (pinfunction "2_2") (pintype "passive"))
    )
    (net (code "225") (name "unconnected-(R82-Pad1)") (class "Default")
      (node (ref "R82") (pin "1") (pinfunction "1_1") (pintype "passive"))
    )
    (net (code "226") (name "unconnected-(R83-Pad2)") (class "Default")
      (node (ref "R83") (pin "2") (pinfunction "2_2") (pintype "passive"))
    )
    (net (code "227") (name "unconnected-(R84-Pad1)") (class "Default")
      (node (ref "R84") (pin "1") (pinfunction "1_1") (pintype "passive"))
    )
    (net (code "228") (name "unconnected-(R85-Pad2)") (class "Default")
      (node (ref "R85") (pin "2") (pinfunction "2_2") (pintype "passive"))
    )
    (net (code "229") (name "unconnected-(R86-Pad1)") (class "Default")
      (node (ref "R86") (pin "1") (pinfunction "1_1") (pintype "passive"))
    )
    (net (code "230") (name "unconnected-(R87-Pad2)") (class "Default")
      (node (ref "R87") (pin "2") (pinfunction "2_2") (pintype "passive"))
    )
    (net (code "231") (name "unconnected-(R88-Pad1)") (class "Default")
      (node (ref "R88") (pin "1") (pinfunction "1_1") (pintype "passive"))
    )
    (net (code "232") (name "unconnected-(R89-Pad2)") (class "Default")
      (node (ref "R89") (pin "2") (pinfunction "2_2") (pintype "passive"))
    )
    (net (code "233") (name "unconnected-(R90-Pad1)") (class "Default")
      (node (ref "R90") (pin "1") (pinfunction "1_1") (pintype "passive"))
    )
    (net (code "234") (name "unconnected-(R90-Pad2)") (class "Default")
      (node (ref "R90") (pin "2") (pinfunction "2_2") (pintype "passive"))
    )
    (net (code "235") (name "unconnected-(R91-Pad1)") (class "Default")
      (node (ref "R91") (pin "1") (pinfunction "1_1") (pintype "passive"))
    )
    (net (code "236") (name "unconnected-(R92-Pad2)") (class "Default")
      (node (ref "R92") (pin "2") (pinfunction "2_2") (pintype "passive"))
    )
    (net (code "237") (name "unconnected-(R93-Pad1)") (class "Default")
      (node (ref "R93") (pin "1") (pinfunction "1_1") (pintype "passive"))
    )
    (net (code "238") (name "unconnected-(R94-Pad2)") (class "Default")
      (node (ref "R94") (pin "2") (pinfunction "2_2") (pintype "passive"))
    )
    (net (code "239") (name "unconnected-(R95-Pad1)") (class "Default")
      (node (ref "R95") (pin "1") (pinfunction "1_1") (pintype "passive"))
    )
    (net (code "240") (name "unconnected-(R96-Pad2)") (class "Default")
      (node (ref "R96") (pin "2") (pinfunction "2_2") (pintype "passive"))
    )
    (net (code "241") (name "unconnected-(R97-Pad1)") (class "Default")
      (node (ref "R97") (pin "1") (pinfunction "1_1") (pintype "passive"))
    )
    (net (code "242") (name "unconnected-(R97-Pad2)") (class "Default")
      (node (ref "R97") (pin "2") (pinfunction "2_2") (pintype "passive"))
    )
    (net (code "243") (name "unconnected-(R98-Pad1)") (class "Default")
      (node (ref "R98") (pin "1") (pinfunction "1_1") (pintype "passive"))
    )
    (net (code "244") (name "unconnected-(R99-Pad2)") (class "Default")
      (node (ref "R99") (pin "2") (pinfunction "2_2") (pintype "passive"))
    )
    (net (code "245") (name "unconnected-(R100-Pad1)") (class "Default")
      (node (ref "R100") (pin "1") (pinfunction "1_1") (pintype "passive"))
    )
    (net (code "246") (name "unconnected-(R101-Pad2)") (class "Default")
      (node (ref "R101") (pin "2") (pinfunction "2_2") (pintype "passive"))
    )
    (net (code "247") (name "unconnected-(R102-Pad1)") (class "Default")
      (node (ref "R102") (pin "1") (pinfunction "1_1") (pintype "passive"))
    )
    (net (code "248") (name "unconnected-(R103-Pad2)") (class "Default")
      (node (ref "R103") (pin "2") (pinfunction "2_2") (pintype "passive"))
    )
    (net (code "249") (name "unconnected-(R104-Pad1)") (class "Default")
      (node (ref "R104") (pin "1") (pinfunction "1_1") (pintype "passive"))
    )
    (net (code "250") (name "unconnected-(R104-Pad2)") (class "Default")
      (node (ref "R104") (pin "2") (pinfunction "2_2") (pintype "passive"))
    )
    (net (code "251") (name "unconnected-(R105-Pad1)") (class "Default")
      (node (ref "R105") (pin "1") (pinfunction "1_1") (pintype "passive"))
    )
    (net (code "252") (name "unconnected-(R106-Pad2)") (class "Default")
      (node (ref "R106") (pin "2") (pinfunction "2_2") (pintype "passive"))
    )
    (net (code "253") (name "unconnected-(R107-Pad1)") (class "Default")
      (node (ref "R107") (pin "1") (pinfunction "1_1") (pintype "passive"))
    )
    (net (code "254") (name "unconnected-(R108-Pad2)") (class "Default")
      (node (ref "R108") (pin "2") (pinfunction "2_2") (pintype "passive"))
    )
    (net (code "255") (name "unconnected-(R109-Pad1)") (class "Default")
      (node (ref "R109") (pin "1") (pinfunction "1_1") (pintype "passive"))
    )
    (net (code "256") (name "unconnected-(R110-Pad2)") (class "Default")
      (node (ref "R110") (pin "2") (pinfunction "2_2") (pintype "passive"))
    )
    (net (code "257") (name "unconnected-(R111-Pad1)") (class "Default")
      (node (ref "R111") (pin "1") (pinfunction "1_1") (pintype "passive"))
    )
    (net (code "258") (name "unconnected-(R112-Pad2)") (class "Default")
      (node (ref "R112") (pin "2") (pinfunction "2_2") (pintype "passive"))
    )
    (net (code "259") (name "unconnected-(R113-Pad1)") (class "Default")
      (node (ref "R113") (pin "1") (pinfunction "1_1") (pintype "passive"))
    )
    (net (code "260") (name "unconnected-(R113-Pad2)") (class "Default")
      (node (ref "R113") (pin "2") (pinfunction "2_2") (pintype "passive"))
    )
    (net (code "261") (name "unconnected-(R114-Pad1)") (class "Default")
      (node (ref "R114") (pin "1") (pinfunction "1_1") (pintype "passive"))
    )
    (net (code "262") (name "unconnected-(R115-Pad2)") (class "Default")
      (node (ref "R115") (pin "2") (pinfunction "2_2") (pintype "passive"))
    )
    (net (code "263") (name "unconnected-(R116-Pad1)") (class "Default")
      (node (ref "R116") (pin "1") (pinfunction "1_1") (pintype "passive"))
    )
    (net (code "264") (name "unconnected-(R117-Pad2)") (class "Default")
      (node (ref "R117") (pin "2") (pinfunction "2_2") (pintype "passive"))
    )
    (net (code "265") (name "unconnected-(R118-Pad1)") (class "Default")
      (node (ref "R118") (pin "1") (pinfunction "1_1") (pintype "passive"))
    )
    (net (code "266") (name "unconnected-(R119-Pad2)") (class "Default")
      (node (ref "R119") (pin "2") (pinfunction "2_2") (pintype "passive"))
    )
    (net (code "267") (name "unconnected-(R120-Pad1)") (class "Default")
      (node (ref "R120") (pin "1") (pinfunction "1_1") (pintype "passive"))
    )
    (net (code "268") (name "unconnected-(R120-Pad2)") (class "Default")
      (node (ref "R120") (pin "2") (pinfunction "2_2") (pintype "passive"))
    )
    (net (code "269") (name "unconnected-(R121-Pad1)") (class "Default")
      (node (ref "R121") (pin "1") (pinfunction "1_1") (pintype "passive"))
    )
    (net (code "270") (name "unconnected-(R122-Pad2)") (class "Default")
      (node (ref "R122") (pin "2") (pinfunction "2_2") (pintype "passive"))
    )
    (net (code "271") (name "unconnected-(R123-Pad1)") (class "Default")
      (node (ref "R123") (pin "1") (pinfunction "1_1") (pintype "passive"))
    )
    (net (code "272") (name "unconnected-(R124-Pad2)") (class "Default")
      (node (ref "R124") (pin "2") (pinfunction "2_2") (pintype "passive"))
    )
    (net (code "273") (name "unconnected-(R125-Pad1)") (class "Default")
      (node (ref "R125") (pin "1") (pinfunction "1_1") (pintype "passive"))
    )
    (net (code "274") (name "unconnected-(R126-Pad2)") (class "Default")
      (node (ref "R126") (pin "2") (pinfunction "2_2") (pintype "passive"))
    )
    (net (code "275") (name "unconnected-(R127-Pad1)") (class "Default")
      (node (ref "R127") (pin "1") (pinfunction "1_1") (pintype "passive"))
    )
    (net (code "276") (name "unconnected-(R127-Pad2)") (class "Default")
      (node (ref "R127") (pin "2") (pinfunction "2_2") (pintype "passive"))
    )
    (net (code "277") (name "unconnected-(R128-Pad1)") (class "Default")
      (node (ref "R128") (pin "1") (pinfunction "1_1") (pintype "passive"))
    )
    (net (code "278") (name "unconnected-(R129-Pad2)") (class "Default")
      (node (ref "R129") (pin "2") (pinfunction "2_2") (pintype "passive"))
    )
    (net (code "279") (name "unconnected-(R130-Pad1)") (class "Default")
      (node (ref "R130") (pin "1") (pinfunction "1_1") (pintype "passive"))
    )
    (net (code "280") (name "unconnected-(R131-Pad2)") (class "Default")
      (node (ref "R131") (pin "2") (pinfunction "2_2") (pintype "passive"))
    )
    (net (code "281") (name "unconnected-(R132-Pad1)") (class "Default")
      (node (ref "R132") (pin "1") (pinfunction "1_1") (pintype "passive"))
    )
    (net (code "282") (name "unconnected-(R133-Pad2)") (class "Default")
      (node (ref "R133") (pin "2") (pinfunction "2_2") (pintype "passive"))
    )
    (net (code "283") (name "unconnected-(R134-Pad1)") (class "Default")
      (node (ref "R134") (pin "1") (pinfunction "1_1") (pintype "passive"))
    )
    (net (code "284") (name "unconnected-(R135-Pad2)") (class "Default")
      (node (ref "R135") (pin "2") (pinfunction "2_2") (pintype "passive"))
    )
    (net (code "285") (name "unconnected-(R136-Pad1)") (class "Default")
      (node (ref "R136") (pin "1") (pinfunction "1_1") (pintype "passive"))
    )
    (net (code "286") (name "unconnected-(R136-Pad2)") (class "Default")
      (node (ref "R136") (pin "2") (pinfunction "2_2") (pintype "passive"))
    )
    (net (code "287") (name "unconnected-(R137-Pad1)") (class "Default")
      (node (ref "R137") (pin "1") (pinfunction "1_1") (pintype "passive"))
    )
    (net (code "288") (name "unconnected-(R138-Pad2)") (class "Default")
      (node (ref "R138") (pin "2") (pinfunction "2_2") (pintype "passive"))
    )
    (net (code "289") (name "unconnected-(R139-Pad1)") (class "Default")
      (node (ref "R139") (pin "1") (pinfunction "1_1") (pintype "passive"))
    )
    (net (code "290") (name "unconnected-(R140-Pad2)") (class "Default")
      (node (ref "R140") (pin "2") (pinfunction "2_2") (pintype "passive"))
    )
    (net (code "291") (name "unconnected-(R141-Pad1)") (class "Default")
      (node (ref "R141") (pin "1") (pinfunction "1_1") (pintype "passive"))
    )
    (net (code "292") (name "unconnected-(R142-Pad2)") (class "Default")
      (node (ref "R142") (pin "2") (pinfunction "2_2") (pintype "passive"))
    )
    (net (code "293") (name "unconnected-(R143-Pad1)") (class "Default")
      (node (ref "R143") (pin "1") (pinfunction "1_1") (pintype "passive"))
    )
    (net (code "294") (name "unconnected-(R143-Pad2)") (class "Default")
      (node (ref "R143") (pin "2") (pinfunction "2_2") (pintype "passive"))
    )
    (net (code "295") (name "unconnected-(R144-Pad1)") (class "Default")
      (node (ref "R144") (pin "1") (pinfunction "1_1") (pintype "passive"))
    )
    (net (code "296") (name "unconnected-(R145-Pad2)") (class "Default")
      (node (ref "R145") (pin "2") (pinfunction "2_2") (pintype "passive"))
    )
    (net (code "297") (name "unconnected-(R146-Pad1)") (class "Default")
      (node (ref "R146") (pin "1") (pinfunction "1_1") (pintype "passive"))
    )
    (net (code "298") (name "unconnected-(R147-Pad2)") (class "Default")
      (node (ref "R147") (pin "2") (pinfunction "2_2") (pintype "passive"))
    )
    (net (code "299") (name "unconnected-(R148-Pad1)") (class "Default")
      (node (ref "R148") (pin "1") (pinfunction "1_1") (pintype "passive"))
    )
    (net (code "300") (name "unconnected-(R149-Pad2)") (class "Default")
      (node (ref "R149") (pin "2") (pinfunction "2_2") (pintype "passive"))
    )
    (net (code "301") (name "unconnected-(R150-Pad1)") (class "Default")
      (node (ref "R150") (pin "1") (pinfunction "1_1") (pintype "passive"))
    )
    (net (code "302") (name "unconnected-(R150-Pad2)") (class "Default")
      (node (ref "R150") (pin "2") (pinfunction "2_2") (pintype "passive"))
    )
    (net (code "303") (name "unconnected-(R151-Pad1)") (class "Default")
      (node (ref "R151") (pin "1") (pinfunction "1_1") (pintype "passive"))
    )
    (net (code "304") (name "unconnected-(R152-Pad2)") (class "Default")
      (node (ref "R152") (pin "2") (pinfunction "2_2") (pintype "passive"))
    )
    (net (code "305") (name "unconnected-(R153-Pad1)") (class "Default")
      (node (ref "R153") (pin "1") (pinfunction "1_1") (pintype "passive"))
    )
    (net (code "306") (name "unconnected-(R154-Pad2)") (class "Default")
      (node (ref "R154") (pin "2") (pinfunction "2_2") (pintype "passive"))
    )
    (net (code "307") (name "unconnected-(R155-Pad1)") (class "Default")
      (node (ref "R155") (pin "1") (pinfunction "1_1") (pintype "passive"))
    )
    (net (code "308") (name "unconnected-(R156-Pad2)") (class "Default")
      (node (ref "R156") (pin "2") (pinfunction "2_2") (pintype "passive"))
    )
    (net (code "309") (name "unconnected-(R157-Pad1)") (class "Default")
      (node (ref "R157") (pin "1") (pinfunction "1_1") (pintype "passive"))
    )
    (net (code "310") (name "unconnected-(R158-Pad2)") (class "Default")
      (node (ref "R158") (pin "2") (pinfunction "2_2") (pintype "passive"))
    )
    (net (code "311") (name "unconnected-(R159-Pad1)") (class "Default")
      (node (ref "R159") (pin "1") (pinfunction "1_1") (pintype "passive"))
    )
    (net (code "312") (name "unconnected-(R160-Pad2)") (class "Default")
      (node (ref "R160") (pin "2") (pinfunction "2_2") (pintype "passive"))
    )
    (net (code "313") (name "unconnected-(R161-Pad1)") (class "Default")
      (node (ref "R161") (pin "1") (pinfunction "1_1") (pintype "passive"))
    )
    (net (code "314") (name "unconnected-(R161-Pad2)") (class "Default")
      (node (ref "R161") (pin "2") (pinfunction "2_2") (pintype "passive"))
    )
    (net (code "315") (name "unconnected-(R162-Pad1)") (class "Default")
      (node (ref "R162") (pin "1") (pinfunction "1_1") (pintype "passive"))
    )
    (net (code "316") (name "unconnected-(R163-Pad2)") (class "Default")
      (node (ref "R163") (pin "2") (pinfunction "2_2") (pintype "passive"))
    )
    (net (code "317") (name "unconnected-(R164-Pad1)") (class "Default")
      (node (ref "R164") (pin "1") (pinfunction "1_1") (pintype "passive"))
    )
    (net (code "318") (name "unconnected-(R165-Pad2)") (class "Default")
      (node (ref "R165") (pin "2") (pinfunction "2_2") (pintype "passive"))
    )
    (net (code "319") (name "unconnected-(R166-Pad1)") (class "Default")
      (node (ref "R166") (pin "1") (pinfunction "1_1") (pintype "passive"))
    )
    (net (code "320") (name "unconnected-(R167-Pad2)") (class "Default")
      (node (ref "R167") (pin "2") (pinfunction "2_2") (pintype "passive"))
    )
    (net (code "321") (name "unconnected-(R168-Pad1)") (class "Default")
      (node (ref "R168") (pin "1") (pinfunction "1_1") (pintype "passive"))
    )
    (net (code "322") (name "unconnected-(R169-Pad2)") (class "Default")
      (node (ref "R169") (pin "2") (pinfunction "2_2") (pintype "passive"))
    )
    (net (code "323") (name "unconnected-(R170-Pad1)") (class "Default")
      (node (ref "R170") (pin "1") (pinfunction "1_1") (pintype "passive"))
    )
    (net (code "324") (name "unconnected-(R170-Pad2)") (class "Default")
      (node (ref "R170") (pin "2") (pinfunction "2_2") (pintype "passive"))
    )
    (net (code "325") (name "unconnected-(R171-Pad1)") (class "Default")
      (node (ref "R171") (pin "1") (pinfunction "1_1") (pintype "passive"))
    )
    (net (code "326") (name "unconnected-(R172-Pad2)") (class "Default")
      (node (ref "R172") (pin "2") (pinfunction "2_2") (pintype "passive"))
    )
    (net (code "327") (name "unconnected-(R173-Pad1)") (class "Default")
      (node (ref "R173") (pin "1") (pinfunction "1_1") (pintype "passive"))
    )
    (net (code "328") (name "unconnected-(R174-Pad2)") (class "Default")
      (node (ref "R174") (pin "2") (pinfunction "2_2") (pintype "passive"))
    )
    (net (code "329") (name "unconnected-(R175-Pad1)") (class "Default")
      (node (ref "R175") (pin "1") (pinfunction "1_1") (pintype "passive"))
    )
    (net (code "330") (name "unconnected-(R176-Pad2)") (class "Default")
      (node (ref "R176") (pin "2") (pinfunction "2_2") (pintype "passive"))
    )
    (net (code "331") (name "unconnected-(R177-Pad1)") (class "Default")
      (node (ref "R177") (pin "1") (pinfunction "1_1") (pintype "passive"))
    )
    (net (code "332") (name "unconnected-(R177-Pad2)") (class "Default")
      (node (ref "R177") (pin "2") (pinfunction "2_2") (pintype "passive"))
    )
    (net (code "333") (name "unconnected-(R178-Pad1)") (class "Default")
      (node (ref "R178") (pin "1") (pinfunction "1_1") (pintype "passive"))
    )
    (net (code "334") (name "unconnected-(R179-Pad2)") (class "Default")
      (node (ref "R179") (pin "2") (pinfunction "2_2") (pintype "passive"))
    )
    (net (code "335") (name "unconnected-(R180-Pad1)") (class "Default")
      (node (ref "R180") (pin "1") (pinfunction "1_1") (pintype "passive"))
    )
    (net (code "336") (name "unconnected-(R181-Pad2)") (class "Default")
      (node (ref "R181") (pin "2") (pinfunction "2_2") (pintype "passive"))
    )
    (net (code "337") (name "unconnected-(R182-Pad1)") (class "Default")
      (node (ref "R182") (pin "1") (pinfunction "1_1") (pintype "passive"))
    )
    (net (code "338") (name "unconnected-(R183-Pad2)") (class "Default")
      (node (ref "R183") (pin "2") (pinfunction "2_2") (pintype "passive"))
    )
    (net (code "339") (name "unconnected-(R184-Pad1)") (class "Default")
      (node (ref "R184") (pin "1") (pinfunction "1_1") (pintype "passive"))
    )
    (net (code "340") (name "unconnected-(R184-Pad2)") (class "Default")
      (node (ref "R184") (pin "2") (pinfunction "2_2") (pintype "passive"))
    )
    (net (code "341") (name "unconnected-(R185-Pad1)") (class "Default")
      (node (ref "R185") (pin "1") (pinfunction "1_1") (pintype "passive"))
    )
    (net (code "342") (name "unconnected-(R186-Pad2)") (class "Default")
      (node (ref "R186") (pin "2") (pinfunction "2_2") (pintype "passive"))
    )
    (net (code "343") (name "unconnected-(R187-Pad1)") (class "Default")
      (node (ref "R187") (pin "1") (pinfunction "1_1") (pintype "passive"))
    )
    (net (code "344") (name "unconnected-(R188-Pad2)") (class "Default")
      (node (ref "R188") (pin "2") (pinfunction "2_2") (pintype "passive"))
    )
    (net (code "345") (name "unconnected-(R189-Pad1)") (class "Default")
      (node (ref "R189") (pin "1") (pinfunction "1_1") (pintype "passive"))
    )
    (net (code "346") (name "unconnected-(R190-Pad2)") (class "Default")
      (node (ref "R190") (pin "2") (pinfunction "2_2") (pintype "passive"))
    )
    (net (code "347") (name "unconnected-(R191-Pad1)") (class "Default")
      (node (ref "R191") (pin "1") (pinfunction "1_1") (pintype "passive"))
    )
    (net (code "348") (name "unconnected-(R191-Pad2)") (class "Default")
      (node (ref "R191") (pin "2") (pinfunction "2_2") (pintype "passive"))
    )
  )
)
